# ProPrj_Sandro_OrangePi_CM5_Carrier_Board.net
KiCad netlist of a schematic drawn in EasyEDA Pro
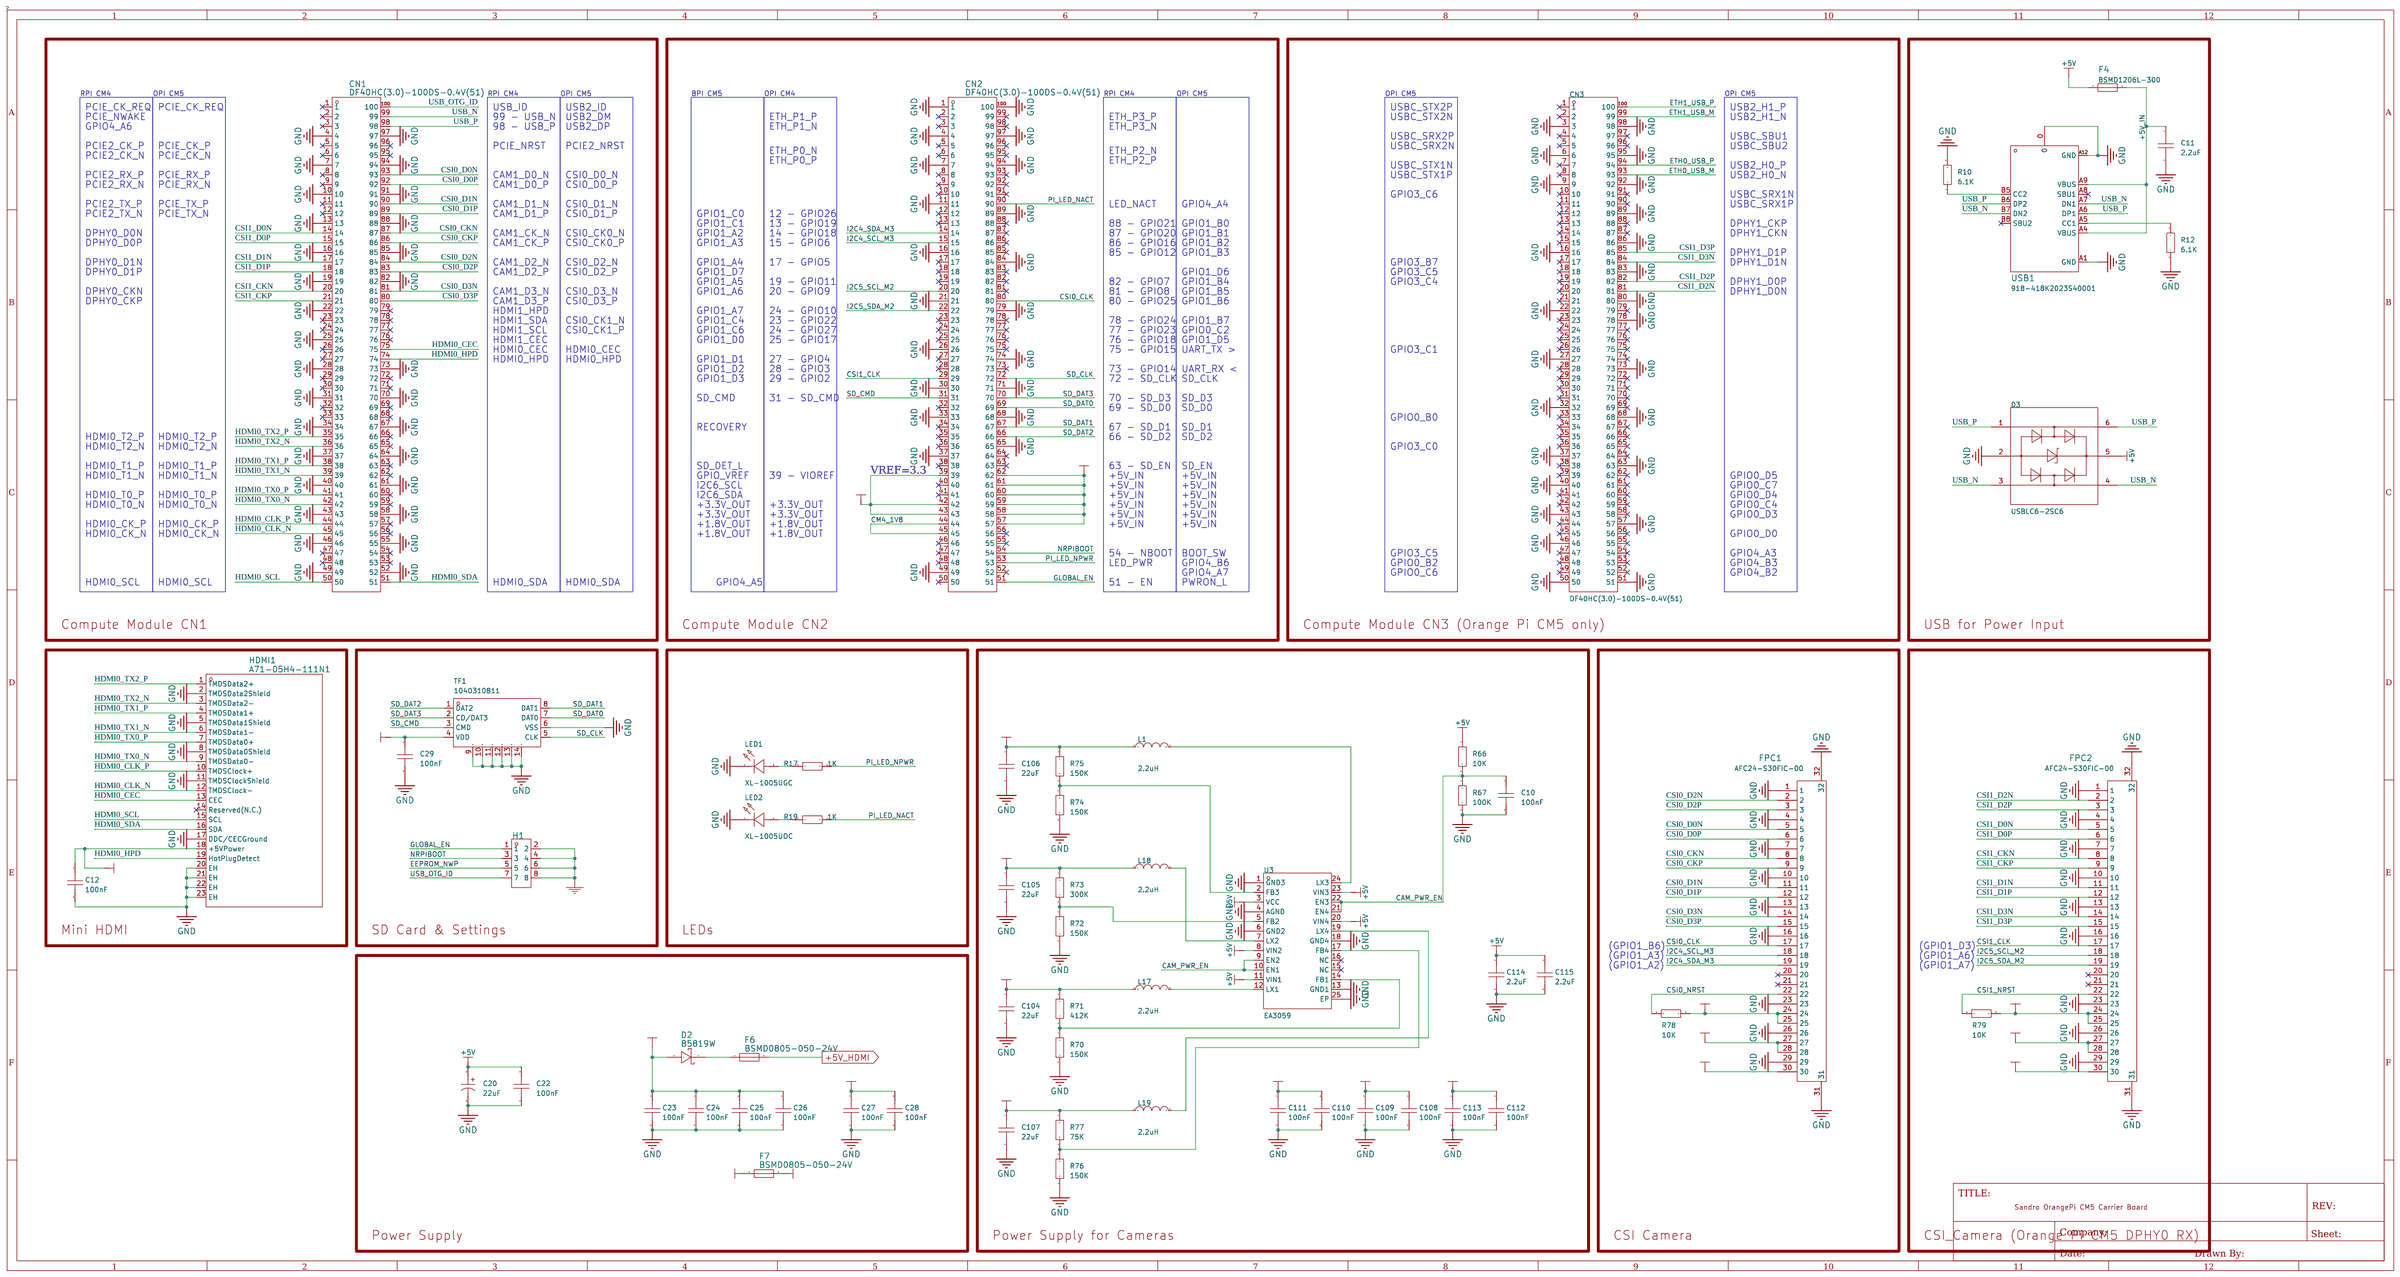
[diagram p0: CM4 Carrier]
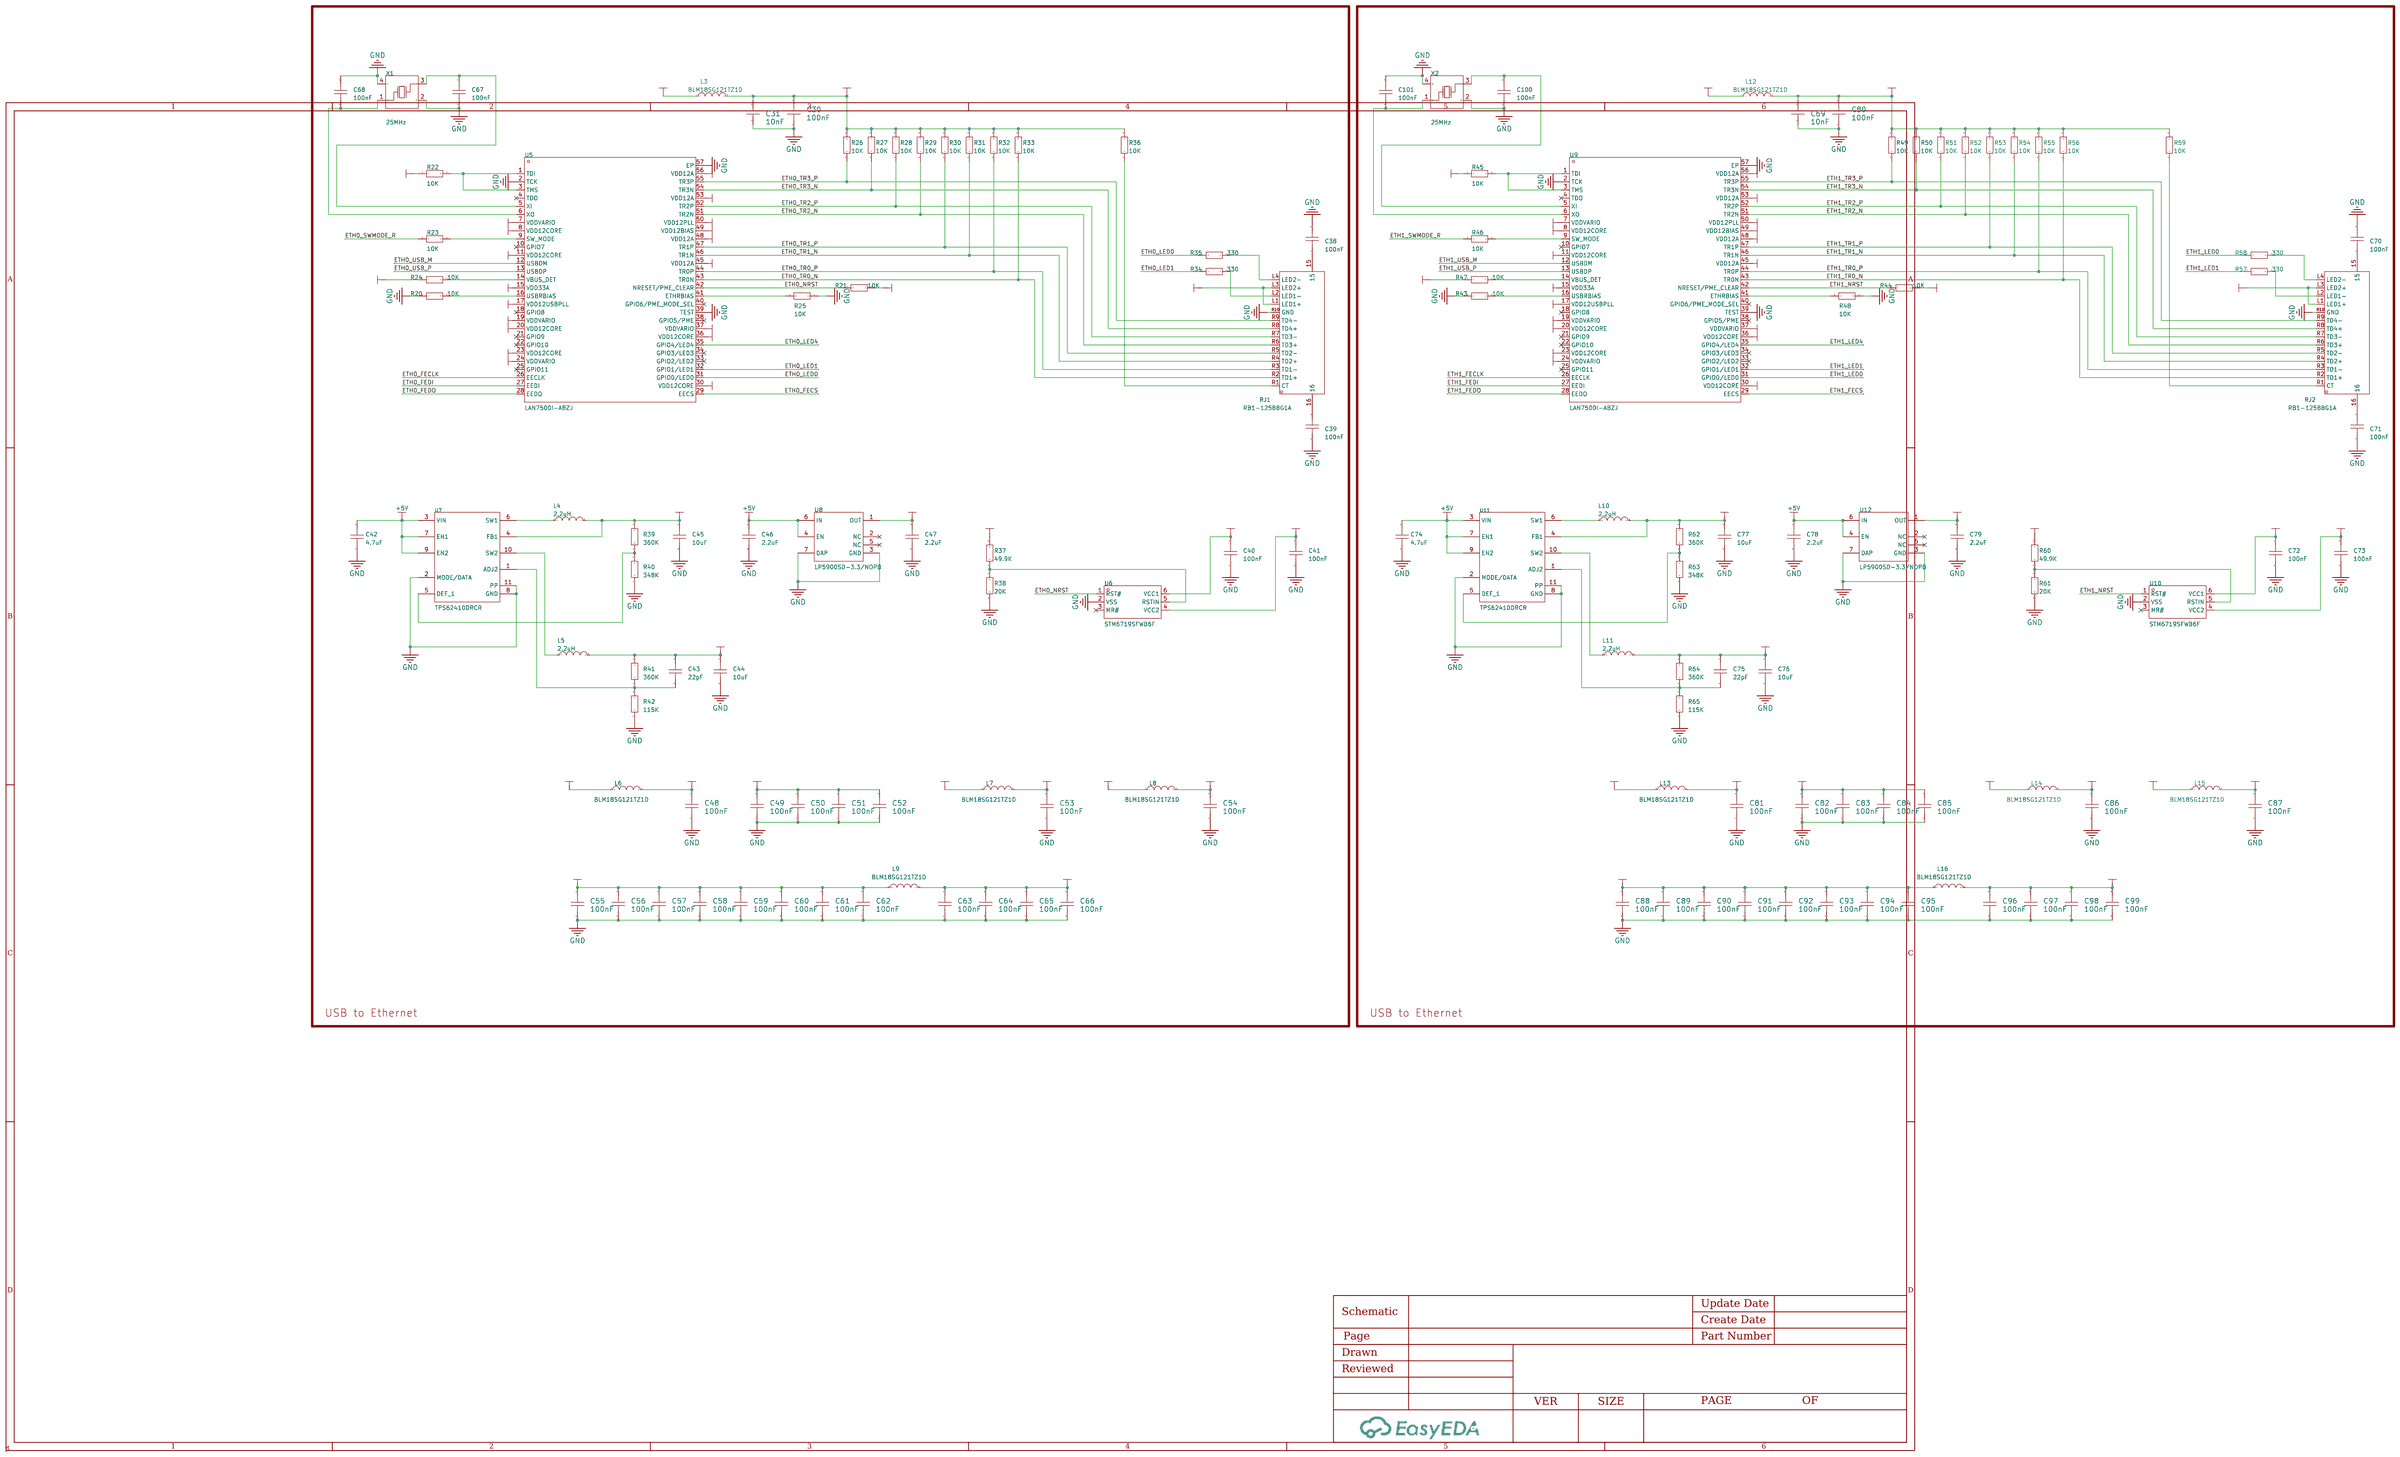
[diagram p1: 2.Ethernet]

(export (version "E")
  (design (tool "Eeschema 10.0.6"))
  (components
    (comp (ref "C10")
      (value "100nF")
      (footprint "easyedapro:C0402")
      (libsource (lib "easyedapro") (part "CAP"))
    )
    (comp (ref "C11")
      (value "2.2uF")
      (footprint "easyedapro:C0402")
      (libsource (lib "easyedapro") (part "CAP"))
    )
    (comp (ref "C12")
      (value "100nF")
      (footprint "easyedapro:C0402")
      (libsource (lib "easyedapro") (part "CAP"))
    )
    (comp (ref "C20")
      (value "22uF")
      (footprint "easyedapro:CAP-SMD_L3.2-W1.6")
      (fields
        (field (name "Manufacturer Part") "CA45-A-16V-22uF-K")
        (field (name "Manufacturer") "CEC(振华新云)")
      )
      (libsource (lib "easyedapro") (part "CA45-A-16V-22UF-K"))
    )
    (comp (ref "C22")
      (value "100nF")
      (footprint "easyedapro:C0402")
      (libsource (lib "easyedapro") (part "CAP"))
    )
    (comp (ref "C23")
      (value "100nF")
      (footprint "easyedapro:C0402")
      (libsource (lib "easyedapro") (part "CAP"))
    )
    (comp (ref "C24")
      (value "100nF")
      (footprint "easyedapro:C0402")
      (libsource (lib "easyedapro") (part "CAP"))
    )
    (comp (ref "C25")
      (value "100nF")
      (footprint "easyedapro:C0402")
      (libsource (lib "easyedapro") (part "CAP"))
    )
    (comp (ref "C26")
      (value "100nF")
      (footprint "easyedapro:C0402")
      (libsource (lib "easyedapro") (part "CAP"))
    )
    (comp (ref "C27")
      (value "100nF")
      (footprint "easyedapro:C0402")
      (libsource (lib "easyedapro") (part "CAP"))
    )
    (comp (ref "C28")
      (value "100nF")
      (footprint "easyedapro:C0402")
      (libsource (lib "easyedapro") (part "CAP"))
    )
    (comp (ref "C29")
      (value "100nF")
      (footprint "easyedapro:C0402")
      (libsource (lib "easyedapro") (part "CAP"))
    )
    (comp (ref "C104")
      (value "22uF")
      (footprint "easyedapro:C0402")
      (libsource (lib "easyedapro") (part "CAP"))
    )
    (comp (ref "C105")
      (value "22uF")
      (footprint "easyedapro:C0402")
      (libsource (lib "easyedapro") (part "CAP"))
    )
    (comp (ref "C106")
      (value "22uF")
      (footprint "easyedapro:C0402")
      (libsource (lib "easyedapro") (part "CAP"))
    )
    (comp (ref "C107")
      (value "22uF")
      (footprint "easyedapro:C0402")
      (libsource (lib "easyedapro") (part "CAP"))
    )
    (comp (ref "C108")
      (value "100nF")
      (footprint "easyedapro:C0402")
      (libsource (lib "easyedapro") (part "CAP"))
    )
    (comp (ref "C109")
      (value "100nF")
      (footprint "easyedapro:C0402")
      (libsource (lib "easyedapro") (part "CAP"))
    )
    (comp (ref "C110")
      (value "100nF")
      (footprint "easyedapro:C0402")
      (libsource (lib "easyedapro") (part "CAP"))
    )
    (comp (ref "C111")
      (value "100nF")
      (footprint "easyedapro:C0402")
      (libsource (lib "easyedapro") (part "CAP"))
    )
    (comp (ref "C112")
      (value "100nF")
      (footprint "easyedapro:C0402")
      (libsource (lib "easyedapro") (part "CAP"))
    )
    (comp (ref "C113")
      (value "100nF")
      (footprint "easyedapro:C0402")
      (libsource (lib "easyedapro") (part "CAP"))
    )
    (comp (ref "C114")
      (value "2.2uF")
      (footprint "easyedapro:C0402")
      (libsource (lib "easyedapro") (part "CAP"))
    )
    (comp (ref "C115")
      (value "2.2uF")
      (footprint "easyedapro:C0402")
      (libsource (lib "easyedapro") (part "CAP"))
    )
    (comp (ref "CN1")
      (value "DF40HC(3.0)-100DS-0.4V(51)")
      (footprint "easyedapro:CONN-SMD_DF40HC-3.0-100DS-0.4V-51")
      (fields (field (name "Manufacturer") "HRS(广濑)"))
      (libsource (lib "easyedapro") (part "DF40HC(3.0)-100DS-0.4V(51)"))
    )
    (comp (ref "CN2")
      (value "DF40HC(3.0)-100DS-0.4V(51)")
      (footprint "easyedapro:CONN-SMD_DF40HC-3.0-100DS-0.4V-51")
      (fields (field (name "Manufacturer") "HRS(广濑)"))
      (libsource (lib "easyedapro") (part "DF40HC(3.0)-100DS-0.4V(51)"))
    )
    (comp (ref "CN3")
      (value "DF40HC(3.0)-100DS-0.4V(51)")
      (footprint "easyedapro:CONN-SMD_DF40HC-3.0-100DS-0.4V-51")
      (fields (field (name "Manufacturer") "HRS(广濑)"))
      (libsource (lib "") (part "DF40HC(3.0)-100DS-0.4V(51)_1"))
    )
    (comp (ref "D2")
      (value "B5819W")
      (footprint "easyedapro:SOD-123_L2.7-W1.6-LS3.7-RD-1")
      (fields (field (name "Manufacturer") "CJ"))
      (libsource (lib "easyedapro") (part "B5819W"))
    )
    (comp (ref "D3")
      (value "USBLC6-2SC6")
      (footprint "easyedapro:SOT-23-6_L2.9-W1.6-P0.95-LS2.8-BL")
      (fields (field (name "Manufacturer") "ST(意法半导体)"))
      (libsource (lib "easyedapro") (part "USBLC6-2SC6"))
    )
    (comp (ref "F4")
      (value "BSMD1206L-300")
      (footprint "easyedapro:F1206")
      (fields (field (name "Manufacturer") "BHFUSE(佰宏)"))
      (libsource (lib "easyedapro") (part "BSMD1206L-300"))
    )
    (comp (ref "F6")
      (value "BSMD0805-050-24V")
      (footprint "easyedapro:F0805")
      (fields (field (name "Manufacturer") "BHFUSE"))
      (libsource (lib "easyedapro") (part "BSMD0805-050-24V"))
    )
    (comp (ref "F7")
      (value "BSMD0805-050-24V")
      (footprint "easyedapro:F0805")
      (fields (field (name "Manufacturer") "BHFUSE"))
      (libsource (lib "easyedapro") (part "BSMD0805-050-24V"))
    )
    (comp (ref "FPC1")
      (value "AFC24-S30FIC-00")
      (footprint "easyedapro:FPC-SMD_P0.50-30P_QCHF-SM-H2.0")
      (fields (field (name "Manufacturer") "JS(钜硕电子)"))
      (libsource (lib "easyedapro") (part "AFC24-S30FIC-00"))
    )
    (comp (ref "FPC2")
      (value "AFC24-S30FIC-00")
      (footprint "easyedapro:FPC-SMD_P0.50-30P_QCHF-SM-H2.0")
      (fields (field (name "Manufacturer") "JS(钜硕电子)"))
      (libsource (lib "easyedapro") (part "AFC24-S30FIC-00"))
    )
    (comp (ref "H1")
      (value "2.54-2*4P立贴针")
      (footprint "easyedapro:HDR-SMD_8P-P2.54-V-M-R2-C4-LS7.4")
      (fields (field (name "Manufacturer") "BOOMELE(博穆精密)"))
      (libsource (lib "easyedapro") (part "2.54-2*4P立贴针"))
    )
    (comp (ref "HDMI1")
      (value "A71-05H4-111N1")
      (footprint "easyedapro:HDMI-SMD_A71-05H4-111N1")
      (fields (field (name "Manufacturer") "XKB Connectivity(中国星坤)"))
      (libsource (lib "easyedapro") (part "A71-05H4-111N1"))
    )
    (comp (ref "L1")
      (value "2.2uH")
      (footprint "easyedapro:IND-SMD_L2.0-W1.6")
      (fields
        (field (name "Manufacturer Part") "CKCS201610-2.2uH/M")
        (field (name "Manufacturer") "CENKER(岑科)")
      )
      (libsource (lib "easyedapro") (part "CKCS201610-2.2UH/M-N"))
    )
    (comp (ref "L17")
      (value "2.2uH")
      (footprint "easyedapro:IND-SMD_L2.0-W1.6")
      (fields
        (field (name "Manufacturer Part") "CKCS201610-2.2uH/M")
        (field (name "Manufacturer") "CENKER(岑科)")
      )
      (libsource (lib "easyedapro") (part "CKCS201610-2.2UH/M-N"))
    )
    (comp (ref "L18")
      (value "2.2uH")
      (footprint "easyedapro:IND-SMD_L2.0-W1.6")
      (fields
        (field (name "Manufacturer Part") "CKCS201610-2.2uH/M")
        (field (name "Manufacturer") "CENKER(岑科)")
      )
      (libsource (lib "easyedapro") (part "CKCS201610-2.2UH/M-N"))
    )
    (comp (ref "L19")
      (value "2.2uH")
      (footprint "easyedapro:IND-SMD_L2.0-W1.6")
      (fields
        (field (name "Manufacturer Part") "CKCS201610-2.2uH/M")
        (field (name "Manufacturer") "CENKER(岑科)")
      )
      (libsource (lib "easyedapro") (part "CKCS201610-2.2UH/M-N"))
    )
    (comp (ref "LED1")
      (value "XL-1005UGC")
      (footprint "easyedapro:LED0402-RD_GREEN")
      (fields (field (name "Manufacturer") "XINGLIGHT(成兴光)"))
      (libsource (lib "easyedapro") (part "XL-1005UGC"))
    )
    (comp (ref "LED2")
      (value "XL-1005UOC")
      (footprint "easyedapro:LED0402-RD_ORANGE")
      (fields (field (name "Manufacturer") "XINGLIGHT(成兴光)"))
      (libsource (lib "easyedapro") (part "XL-1005UOC"))
    )
    (comp (ref "R10")
      (value "6.1K")
      (footprint "easyedapro:R0201")
      (libsource (lib "easyedapro") (part "Res"))
    )
    (comp (ref "R12")
      (value "6.1K")
      (footprint "easyedapro:R0201")
      (libsource (lib "easyedapro") (part "Res"))
    )
    (comp (ref "R17") (value "1K") (footprint "easyedapro:R0201") (libsource (lib "easyedapro") (part "Res")))
    (comp (ref "R19") (value "1K") (footprint "easyedapro:R0201") (libsource (lib "easyedapro") (part "Res")))
    (comp (ref "R66")
      (value "10K")
      (footprint "easyedapro:R0201")
      (libsource (lib "easyedapro") (part "Res"))
    )
    (comp (ref "R67")
      (value "100K")
      (footprint "easyedapro:R0201")
      (libsource (lib "easyedapro") (part "Res"))
    )
    (comp (ref "R70")
      (value "150K")
      (footprint "easyedapro:R0201")
      (libsource (lib "easyedapro") (part "Res"))
    )
    (comp (ref "R71")
      (value "412K")
      (footprint "easyedapro:R0201")
      (libsource (lib "easyedapro") (part "Res"))
    )
    (comp (ref "R72")
      (value "150K")
      (footprint "easyedapro:R0201")
      (libsource (lib "easyedapro") (part "Res"))
    )
    (comp (ref "R73")
      (value "300K")
      (footprint "easyedapro:R0201")
      (libsource (lib "easyedapro") (part "Res"))
    )
    (comp (ref "R74")
      (value "150K")
      (footprint "easyedapro:R0201")
      (libsource (lib "easyedapro") (part "Res"))
    )
    (comp (ref "R75")
      (value "150K")
      (footprint "easyedapro:R0201")
      (libsource (lib "easyedapro") (part "Res"))
    )
    (comp (ref "R76")
      (value "150K")
      (footprint "easyedapro:R0201")
      (libsource (lib "easyedapro") (part "Res"))
    )
    (comp (ref "R77")
      (value "75K")
      (footprint "easyedapro:R0201")
      (libsource (lib "easyedapro") (part "Res"))
    )
    (comp (ref "R78")
      (value "10K")
      (footprint "easyedapro:R0201")
      (libsource (lib "easyedapro") (part "Res"))
    )
    (comp (ref "R79")
      (value "10K")
      (footprint "easyedapro:R0201")
      (libsource (lib "easyedapro") (part "Res"))
    )
    (comp (ref "TF1")
      (value "1040310811")
      (footprint "easyedapro:SIM-SMD_8P-1040310811")
      (fields (field (name "Manufacturer") "MOLEX"))
      (libsource (lib "easyedapro") (part "1040310811"))
    )
    (comp (ref "U3")
      (value "EA3059")
      (footprint "easyedapro:VQFN-24_L4.0-W4.0-P0.50-TL-EP2.5")
      (fields (field (name "Manufacturer") "everanalog(申风)"))
      (libsource (lib "easyedapro") (part "EA3059"))
    )
    (comp (ref "USB1")
      (value "918-418K2023S40001")
      (footprint "easyedapro:USB-C-SMD_TYPE-C-USB-17")
      (fields (field (name "Manufacturer") "精拓金"))
      (libsource (lib "easyedapro") (part "USB3.1C16PFSMT"))
    )
    (comp (ref "C30")
      (value "100nF")
      (footprint "easyedapro:C0402")
      (fields
        (field (name "Manufacturer Part") "GRM155R71H104KE14D")
        (field (name "Manufacturer") "muRata(村田)")
      )
      (libsource (lib "easyedapro") (part "GRM155R71H104KE14D"))
    )
    (comp (ref "C31")
      (value "10nF")
      (footprint "easyedapro:C0402")
      (fields
        (field (name "Manufacturer Part") "GRM155R71H103KA88D")
        (field (name "Manufacturer") "muRata(村田)")
      )
      (libsource (lib "easyedapro") (part "GRM155R71H103KA88D"))
    )
    (comp (ref "C38")
      (value "100nF")
      (footprint "easyedapro:C0402")
      (libsource (lib "easyedapro") (part "CAP"))
    )
    (comp (ref "C39")
      (value "100nF")
      (footprint "easyedapro:C0402")
      (libsource (lib "easyedapro") (part "CAP"))
    )
    (comp (ref "C40")
      (value "100nF")
      (footprint "easyedapro:C0402")
      (libsource (lib "easyedapro") (part "CAP"))
    )
    (comp (ref "C41")
      (value "100nF")
      (footprint "easyedapro:C0402")
      (libsource (lib "easyedapro") (part "CAP"))
    )
    (comp (ref "C42")
      (value "4.7uF")
      (footprint "easyedapro:C0603")
      (fields
        (field (name "Manufacturer Part") "GRM188Z71C475KE21D")
        (field (name "Manufacturer") "muRata(村田)")
      )
      (libsource (lib "easyedapro") (part "GRM188Z71C475KE21D"))
    )
    (comp (ref "C43")
      (value "22pF")
      (footprint "easyedapro:C0402")
      (libsource (lib "easyedapro") (part "CAP"))
    )
    (comp (ref "C44")
      (value "10uF")
      (footprint "easyedapro:C0402")
      (libsource (lib "easyedapro") (part "CAP"))
    )
    (comp (ref "C45")
      (value "10uF")
      (footprint "easyedapro:C0402")
      (libsource (lib "easyedapro") (part "CAP"))
    )
    (comp (ref "C46")
      (value "2.2uF")
      (footprint "easyedapro:C0402")
      (libsource (lib "easyedapro") (part "CAP"))
    )
    (comp (ref "C47")
      (value "2.2uF")
      (footprint "easyedapro:C0402")
      (libsource (lib "easyedapro") (part "CAP"))
    )
    (comp (ref "C48")
      (value "100nF")
      (footprint "easyedapro:C0402")
      (fields
        (field (name "Manufacturer Part") "GRM155R71H104KE14D")
        (field (name "Manufacturer") "muRata(村田)")
        (field (name "Tolerance") "±10%")
      )
      (libsource (lib "easyedapro") (part "GRM155R71H104KE14D"))
    )
    (comp (ref "C49")
      (value "100nF")
      (footprint "easyedapro:C0402")
      (fields
        (field (name "Manufacturer Part") "GRM155R71H104KE14D")
        (field (name "Manufacturer") "muRata(村田)")
        (field (name "Tolerance") "±10%")
      )
      (libsource (lib "easyedapro") (part "GRM155R71H104KE14D"))
    )
    (comp (ref "C50")
      (value "100nF")
      (footprint "easyedapro:C0402")
      (fields
        (field (name "Manufacturer Part") "GRM155R71H104KE14D")
        (field (name "Manufacturer") "muRata(村田)")
        (field (name "Tolerance") "±10%")
      )
      (libsource (lib "easyedapro") (part "GRM155R71H104KE14D"))
    )
    (comp (ref "C51")
      (value "100nF")
      (footprint "easyedapro:C0402")
      (fields
        (field (name "Manufacturer Part") "GRM155R71H104KE14D")
        (field (name "Manufacturer") "muRata(村田)")
        (field (name "Tolerance") "±10%")
      )
      (libsource (lib "easyedapro") (part "GRM155R71H104KE14D"))
    )
    (comp (ref "C52")
      (value "100nF")
      (footprint "easyedapro:C0402")
      (fields
        (field (name "Manufacturer Part") "GRM155R71H104KE14D")
        (field (name "Manufacturer") "muRata(村田)")
        (field (name "Tolerance") "±10%")
      )
      (libsource (lib "easyedapro") (part "GRM155R71H104KE14D"))
    )
    (comp (ref "C53")
      (value "100nF")
      (footprint "easyedapro:C0402")
      (fields
        (field (name "Manufacturer Part") "GRM155R71H104KE14D")
        (field (name "Manufacturer") "muRata(村田)")
        (field (name "Tolerance") "±10%")
      )
      (libsource (lib "easyedapro") (part "GRM155R71H104KE14D"))
    )
    (comp (ref "C54")
      (value "100nF")
      (footprint "easyedapro:C0402")
      (fields
        (field (name "Manufacturer Part") "GRM155R71H104KE14D")
        (field (name "Manufacturer") "muRata(村田)")
        (field (name "Tolerance") "±10%")
      )
      (libsource (lib "easyedapro") (part "GRM155R71H104KE14D"))
    )
    (comp (ref "C55")
      (value "100nF")
      (footprint "easyedapro:C0402")
      (fields
        (field (name "Manufacturer Part") "GRM155R71H104KE14D")
        (field (name "Manufacturer") "muRata(村田)")
        (field (name "Tolerance") "±10%")
      )
      (libsource (lib "easyedapro") (part "GRM155R71H104KE14D"))
    )
    (comp (ref "C56")
      (value "100nF")
      (footprint "easyedapro:C0402")
      (fields
        (field (name "Manufacturer Part") "GRM155R71H104KE14D")
        (field (name "Manufacturer") "muRata(村田)")
        (field (name "Tolerance") "±10%")
      )
      (libsource (lib "easyedapro") (part "GRM155R71H104KE14D"))
    )
    (comp (ref "C57")
      (value "100nF")
      (footprint "easyedapro:C0402")
      (fields
        (field (name "Manufacturer Part") "GRM155R71H104KE14D")
        (field (name "Manufacturer") "muRata(村田)")
        (field (name "Tolerance") "±10%")
      )
      (libsource (lib "easyedapro") (part "GRM155R71H104KE14D"))
    )
    (comp (ref "C58")
      (value "100nF")
      (footprint "easyedapro:C0402")
      (fields
        (field (name "Manufacturer Part") "GRM155R71H104KE14D")
        (field (name "Manufacturer") "muRata(村田)")
        (field (name "Tolerance") "±10%")
      )
      (libsource (lib "easyedapro") (part "GRM155R71H104KE14D"))
    )
    (comp (ref "C59")
      (value "100nF")
      (footprint "easyedapro:C0402")
      (fields
        (field (name "Manufacturer Part") "GRM155R71H104KE14D")
        (field (name "Manufacturer") "muRata(村田)")
        (field (name "Tolerance") "±10%")
      )
      (libsource (lib "easyedapro") (part "GRM155R71H104KE14D"))
    )
    (comp (ref "C60")
      (value "100nF")
      (footprint "easyedapro:C0402")
      (fields
        (field (name "Manufacturer Part") "GRM155R71H104KE14D")
        (field (name "Manufacturer") "muRata(村田)")
        (field (name "Tolerance") "±10%")
      )
      (libsource (lib "easyedapro") (part "GRM155R71H104KE14D"))
    )
    (comp (ref "C61")
      (value "100nF")
      (footprint "easyedapro:C0402")
      (fields
        (field (name "Manufacturer Part") "GRM155R71H104KE14D")
        (field (name "Manufacturer") "muRata(村田)")
        (field (name "Tolerance") "±10%")
      )
      (libsource (lib "easyedapro") (part "GRM155R71H104KE14D"))
    )
    (comp (ref "C62")
      (value "100nF")
      (footprint "easyedapro:C0402")
      (fields
        (field (name "Manufacturer Part") "GRM155R71H104KE14D")
        (field (name "Manufacturer") "muRata(村田)")
        (field (name "Tolerance") "±10%")
      )
      (libsource (lib "easyedapro") (part "GRM155R71H104KE14D"))
    )
    (comp (ref "C63")
      (value "100nF")
      (footprint "easyedapro:C0402")
      (fields
        (field (name "Manufacturer Part") "GRM155R71H104KE14D")
        (field (name "Manufacturer") "muRata(村田)")
        (field (name "Tolerance") "±10%")
      )
      (libsource (lib "easyedapro") (part "GRM155R71H104KE14D"))
    )
    (comp (ref "C64")
      (value "100nF")
      (footprint "easyedapro:C0402")
      (fields
        (field (name "Manufacturer Part") "GRM155R71H104KE14D")
        (field (name "Manufacturer") "muRata(村田)")
        (field (name "Tolerance") "±10%")
      )
      (libsource (lib "easyedapro") (part "GRM155R71H104KE14D"))
    )
    (comp (ref "C65")
      (value "100nF")
      (footprint "easyedapro:C0402")
      (fields
        (field (name "Manufacturer Part") "GRM155R71H104KE14D")
        (field (name "Manufacturer") "muRata(村田)")
        (field (name "Tolerance") "±10%")
      )
      (libsource (lib "easyedapro") (part "GRM155R71H104KE14D"))
    )
    (comp (ref "C66")
      (value "100nF")
      (footprint "easyedapro:C0402")
      (fields
        (field (name "Manufacturer Part") "GRM155R71H104KE14D")
        (field (name "Manufacturer") "muRata(村田)")
        (field (name "Tolerance") "±10%")
      )
      (libsource (lib "easyedapro") (part "GRM155R71H104KE14D"))
    )
    (comp (ref "C67")
      (value "100nF")
      (footprint "easyedapro:C0402")
      (libsource (lib "easyedapro") (part "CAP"))
    )
    (comp (ref "C68")
      (value "100nF")
      (footprint "easyedapro:C0402")
      (libsource (lib "easyedapro") (part "CAP"))
    )
    (comp (ref "C69")
      (value "10nF")
      (footprint "easyedapro:C0402")
      (fields
        (field (name "Manufacturer Part") "GRM155R71H103KA88D")
        (field (name "Manufacturer") "muRata(村田)")
      )
      (libsource (lib "easyedapro") (part "GRM155R71H103KA88D"))
    )
    (comp (ref "C70")
      (value "100nF")
      (footprint "easyedapro:C0402")
      (libsource (lib "easyedapro") (part "CAP"))
    )
    (comp (ref "C71")
      (value "100nF")
      (footprint "easyedapro:C0402")
      (libsource (lib "easyedapro") (part "CAP"))
    )
    (comp (ref "C72")
      (value "100nF")
      (footprint "easyedapro:C0402")
      (libsource (lib "easyedapro") (part "CAP"))
    )
    (comp (ref "C73")
      (value "100nF")
      (footprint "easyedapro:C0402")
      (libsource (lib "easyedapro") (part "CAP"))
    )
    (comp (ref "C74")
      (value "4.7uF")
      (footprint "easyedapro:C0603")
      (fields
        (field (name "Manufacturer Part") "GRM188Z71C475KE21D")
        (field (name "Manufacturer") "muRata(村田)")
      )
      (libsource (lib "easyedapro") (part "GRM188Z71C475KE21D"))
    )
    (comp (ref "C75")
      (value "22pF")
      (footprint "easyedapro:C0402")
      (libsource (lib "easyedapro") (part "CAP"))
    )
    (comp (ref "C76")
      (value "10uF")
      (footprint "easyedapro:C0402")
      (libsource (lib "easyedapro") (part "CAP"))
    )
    (comp (ref "C77")
      (value "10uF")
      (footprint "easyedapro:C0402")
      (libsource (lib "easyedapro") (part "CAP"))
    )
    (comp (ref "C78")
      (value "2.2uF")
      (footprint "easyedapro:C0402")
      (libsource (lib "easyedapro") (part "CAP"))
    )
    (comp (ref "C79")
      (value "2.2uF")
      (footprint "easyedapro:C0402")
      (libsource (lib "easyedapro") (part "CAP"))
    )
    (comp (ref "C80")
      (value "100nF")
      (footprint "easyedapro:C0402")
      (fields
        (field (name "Manufacturer Part") "GRM155R71H104KE14D")
        (field (name "Manufacturer") "muRata(村田)")
      )
      (libsource (lib "easyedapro") (part "GRM155R71H104KE14D"))
    )
    (comp (ref "C81")
      (value "100nF")
      (footprint "easyedapro:C0402")
      (fields
        (field (name "Manufacturer Part") "GRM155R71H104KE14D")
        (field (name "Manufacturer") "muRata(村田)")
        (field (name "Tolerance") "±10%")
      )
      (libsource (lib "easyedapro") (part "GRM155R71H104KE14D"))
    )
    (comp (ref "C82")
      (value "100nF")
      (footprint "easyedapro:C0402")
      (fields
        (field (name "Manufacturer Part") "GRM155R71H104KE14D")
        (field (name "Manufacturer") "muRata(村田)")
        (field (name "Tolerance") "±10%")
      )
      (libsource (lib "easyedapro") (part "GRM155R71H104KE14D"))
    )
    (comp (ref "C83")
      (value "100nF")
      (footprint "easyedapro:C0402")
      (fields
        (field (name "Manufacturer Part") "GRM155R71H104KE14D")
        (field (name "Manufacturer") "muRata(村田)")
        (field (name "Tolerance") "±10%")
      )
      (libsource (lib "easyedapro") (part "GRM155R71H104KE14D"))
    )
    (comp (ref "C84")
      (value "100nF")
      (footprint "easyedapro:C0402")
      (fields
        (field (name "Manufacturer Part") "GRM155R71H104KE14D")
        (field (name "Manufacturer") "muRata(村田)")
        (field (name "Tolerance") "±10%")
      )
      (libsource (lib "easyedapro") (part "GRM155R71H104KE14D"))
    )
    (comp (ref "C85")
      (value "100nF")
      (footprint "easyedapro:C0402")
      (fields
        (field (name "Manufacturer Part") "GRM155R71H104KE14D")
        (field (name "Manufacturer") "muRata(村田)")
        (field (name "Tolerance") "±10%")
      )
      (libsource (lib "easyedapro") (part "GRM155R71H104KE14D"))
    )
    (comp (ref "C86")
      (value "100nF")
      (footprint "easyedapro:C0402")
      (fields
        (field (name "Manufacturer Part") "GRM155R71H104KE14D")
        (field (name "Manufacturer") "muRata(村田)")
        (field (name "Tolerance") "±10%")
      )
      (libsource (lib "easyedapro") (part "GRM155R71H104KE14D"))
    )
    (comp (ref "C87")
      (value "100nF")
      (footprint "easyedapro:C0402")
      (fields
        (field (name "Manufacturer Part") "GRM155R71H104KE14D")
        (field (name "Manufacturer") "muRata(村田)")
        (field (name "Tolerance") "±10%")
      )
      (libsource (lib "easyedapro") (part "GRM155R71H104KE14D"))
    )
    (comp (ref "C88")
      (value "100nF")
      (footprint "easyedapro:C0402")
      (fields
        (field (name "Manufacturer Part") "GRM155R71H104KE14D")
        (field (name "Manufacturer") "muRata(村田)")
        (field (name "Tolerance") "±10%")
      )
      (libsource (lib "easyedapro") (part "GRM155R71H104KE14D"))
    )
    (comp (ref "C89")
      (value "100nF")
      (footprint "easyedapro:C0402")
      (fields
        (field (name "Manufacturer Part") "GRM155R71H104KE14D")
        (field (name "Manufacturer") "muRata(村田)")
        (field (name "Tolerance") "±10%")
      )
      (libsource (lib "easyedapro") (part "GRM155R71H104KE14D"))
    )
    (comp (ref "C90")
      (value "100nF")
      (footprint "easyedapro:C0402")
      (fields
        (field (name "Manufacturer Part") "GRM155R71H104KE14D")
        (field (name "Manufacturer") "muRata(村田)")
        (field (name "Tolerance") "±10%")
      )
      (libsource (lib "easyedapro") (part "GRM155R71H104KE14D"))
    )
    (comp (ref "C91")
      (value "100nF")
      (footprint "easyedapro:C0402")
      (fields
        (field (name "Manufacturer Part") "GRM155R71H104KE14D")
        (field (name "Manufacturer") "muRata(村田)")
        (field (name "Tolerance") "±10%")
      )
      (libsource (lib "easyedapro") (part "GRM155R71H104KE14D"))
    )
    (comp (ref "C92")
      (value "100nF")
      (footprint "easyedapro:C0402")
      (fields
        (field (name "Manufacturer Part") "GRM155R71H104KE14D")
        (field (name "Manufacturer") "muRata(村田)")
        (field (name "Tolerance") "±10%")
      )
      (libsource (lib "easyedapro") (part "GRM155R71H104KE14D"))
    )
    (comp (ref "C93")
      (value "100nF")
      (footprint "easyedapro:C0402")
      (fields
        (field (name "Manufacturer Part") "GRM155R71H104KE14D")
        (field (name "Manufacturer") "muRata(村田)")
        (field (name "Tolerance") "±10%")
      )
      (libsource (lib "easyedapro") (part "GRM155R71H104KE14D"))
    )
    (comp (ref "C94")
      (value "100nF")
      (footprint "easyedapro:C0402")
      (fields
        (field (name "Manufacturer Part") "GRM155R71H104KE14D")
        (field (name "Manufacturer") "muRata(村田)")
        (field (name "Tolerance") "±10%")
      )
      (libsource (lib "easyedapro") (part "GRM155R71H104KE14D"))
    )
    (comp (ref "C95")
      (value "100nF")
      (footprint "easyedapro:C0402")
      (fields
        (field (name "Manufacturer Part") "GRM155R71H104KE14D")
        (field (name "Manufacturer") "muRata(村田)")
        (field (name "Tolerance") "±10%")
      )
      (libsource (lib "easyedapro") (part "GRM155R71H104KE14D"))
    )
    (comp (ref "C96")
      (value "100nF")
      (footprint "easyedapro:C0402")
      (fields
        (field (name "Manufacturer Part") "GRM155R71H104KE14D")
        (field (name "Manufacturer") "muRata(村田)")
        (field (name "Tolerance") "±10%")
      )
      (libsource (lib "easyedapro") (part "GRM155R71H104KE14D"))
    )
    (comp (ref "C97")
      (value "100nF")
      (footprint "easyedapro:C0402")
      (fields
        (field (name "Manufacturer Part") "GRM155R71H104KE14D")
        (field (name "Manufacturer") "muRata(村田)")
        (field (name "Tolerance") "±10%")
      )
      (libsource (lib "easyedapro") (part "GRM155R71H104KE14D"))
    )
    (comp (ref "C98")
      (value "100nF")
      (footprint "easyedapro:C0402")
      (fields
        (field (name "Manufacturer Part") "GRM155R71H104KE14D")
        (field (name "Manufacturer") "muRata(村田)")
        (field (name "Tolerance") "±10%")
      )
      (libsource (lib "easyedapro") (part "GRM155R71H104KE14D"))
    )
    (comp (ref "C99")
      (value "100nF")
      (footprint "easyedapro:C0402")
      (fields
        (field (name "Manufacturer Part") "GRM155R71H104KE14D")
        (field (name "Manufacturer") "muRata(村田)")
        (field (name "Tolerance") "±10%")
      )
      (libsource (lib "easyedapro") (part "GRM155R71H104KE14D"))
    )
    (comp (ref "C100")
      (value "100nF")
      (footprint "easyedapro:C0402")
      (libsource (lib "easyedapro") (part "CAP"))
    )
    (comp (ref "C101")
      (value "100nF")
      (footprint "easyedapro:C0402")
      (libsource (lib "easyedapro") (part "CAP"))
    )
    (comp (ref "L3")
      (value "BLM18SG121TZ1D")
      (footprint "easyedapro:L0603")
      (fields (field (name "Manufacturer") "muRata(村田)"))
      (libsource (lib "easyedapro") (part "BLM18SG121TZ1D"))
    )
    (comp (ref "L4")
      (value "2.2uH")
      (footprint "easyedapro:IND-SMD_L2.0-W1.6")
      (fields
        (field (name "Manufacturer Part") "CKCS201610-2.2uH/M")
        (field (name "Manufacturer") "CENKER(岑科)")
      )
      (libsource (lib "easyedapro") (part "CKCS201610-2.2UH/M-N"))
    )
    (comp (ref "L5")
      (value "2.2uH")
      (footprint "easyedapro:IND-SMD_L2.0-W1.6")
      (fields
        (field (name "Manufacturer Part") "CKCS201610-2.2uH/M")
        (field (name "Manufacturer") "CENKER(岑科)")
      )
      (libsource (lib "easyedapro") (part "CKCS201610-2.2UH/M-N"))
    )
    (comp (ref "L6")
      (value "BLM18SG121TZ1D")
      (footprint "easyedapro:L0603")
      (fields (field (name "Manufacturer") "muRata(村田)"))
      (libsource (lib "easyedapro") (part "BLM18SG121TZ1D"))
    )
    (comp (ref "L7")
      (value "BLM18SG121TZ1D")
      (footprint "easyedapro:L0603")
      (fields (field (name "Manufacturer") "muRata(村田)"))
      (libsource (lib "easyedapro") (part "BLM18SG121TZ1D"))
    )
    (comp (ref "L8")
      (value "BLM18SG121TZ1D")
      (footprint "easyedapro:L0603")
      (fields (field (name "Manufacturer") "muRata(村田)"))
      (libsource (lib "easyedapro") (part "BLM18SG121TZ1D"))
    )
    (comp (ref "L9")
      (value "BLM18SG121TZ1D")
      (footprint "easyedapro:L0603")
      (fields (field (name "Manufacturer") "muRata(村田)"))
      (libsource (lib "easyedapro") (part "BLM18SG121TZ1D"))
    )
    (comp (ref "L10")
      (value "2.2uH")
      (footprint "easyedapro:IND-SMD_L2.0-W1.6")
      (fields
        (field (name "Manufacturer Part") "CKCS201610-2.2uH/M")
        (field (name "Manufacturer") "CENKER(岑科)")
      )
      (libsource (lib "easyedapro") (part "CKCS201610-2.2UH/M-N"))
    )
    (comp (ref "L11")
      (value "2.2uH")
      (footprint "easyedapro:IND-SMD_L2.0-W1.6")
      (fields
        (field (name "Manufacturer Part") "CKCS201610-2.2uH/M")
        (field (name "Manufacturer") "CENKER(岑科)")
      )
      (libsource (lib "easyedapro") (part "CKCS201610-2.2UH/M-N"))
    )
    (comp (ref "L12")
      (value "BLM18SG121TZ1D")
      (footprint "easyedapro:L0603")
      (fields (field (name "Manufacturer") "muRata(村田)"))
      (libsource (lib "easyedapro") (part "BLM18SG121TZ1D"))
    )
    (comp (ref "L13")
      (value "BLM18SG121TZ1D")
      (footprint "easyedapro:L0603")
      (fields (field (name "Manufacturer") "muRata(村田)"))
      (libsource (lib "easyedapro") (part "BLM18SG121TZ1D"))
    )
    (comp (ref "L14")
      (value "BLM18SG121TZ1D")
      (footprint "easyedapro:L0603")
      (fields (field (name "Manufacturer") "muRata(村田)"))
      (libsource (lib "easyedapro") (part "BLM18SG121TZ1D"))
    )
    (comp (ref "L15")
      (value "BLM18SG121TZ1D")
      (footprint "easyedapro:L0603")
      (fields (field (name "Manufacturer") "muRata(村田)"))
      (libsource (lib "easyedapro") (part "BLM18SG121TZ1D"))
    )
    (comp (ref "L16")
      (value "BLM18SG121TZ1D")
      (footprint "easyedapro:L0603")
      (fields (field (name "Manufacturer") "muRata(村田)"))
      (libsource (lib "easyedapro") (part "BLM18SG121TZ1D"))
    )
    (comp (ref "R20")
      (value "10K")
      (footprint "easyedapro:R0201")
      (libsource (lib "easyedapro") (part "Res"))
    )
    (comp (ref "R21")
      (value "10K")
      (footprint "easyedapro:R0201")
      (libsource (lib "easyedapro") (part "Res"))
    )
    (comp (ref "R22")
      (value "10K")
      (footprint "easyedapro:R0201")
      (libsource (lib "easyedapro") (part "Res"))
    )
    (comp (ref "R23")
      (value "10K")
      (footprint "easyedapro:R0201")
      (libsource (lib "easyedapro") (part "Res"))
    )
    (comp (ref "R24")
      (value "10K")
      (footprint "easyedapro:R0201")
      (libsource (lib "easyedapro") (part "Res"))
    )
    (comp (ref "R25")
      (value "10K")
      (footprint "easyedapro:R0201")
      (libsource (lib "easyedapro") (part "Res"))
    )
    (comp (ref "R26")
      (value "10K")
      (footprint "easyedapro:R0201")
      (libsource (lib "easyedapro") (part "Res"))
    )
    (comp (ref "R27")
      (value "10K")
      (footprint "easyedapro:R0201")
      (libsource (lib "easyedapro") (part "Res"))
    )
    (comp (ref "R28")
      (value "10K")
      (footprint "easyedapro:R0201")
      (libsource (lib "easyedapro") (part "Res"))
    )
    (comp (ref "R29")
      (value "10K")
      (footprint "easyedapro:R0201")
      (libsource (lib "easyedapro") (part "Res"))
    )
    (comp (ref "R30")
      (value "10K")
      (footprint "easyedapro:R0201")
      (libsource (lib "easyedapro") (part "Res"))
    )
    (comp (ref "R31")
      (value "10K")
      (footprint "easyedapro:R0201")
      (libsource (lib "easyedapro") (part "Res"))
    )
    (comp (ref "R32")
      (value "10K")
      (footprint "easyedapro:R0201")
      (libsource (lib "easyedapro") (part "Res"))
    )
    (comp (ref "R33")
      (value "10K")
      (footprint "easyedapro:R0201")
      (libsource (lib "easyedapro") (part "Res"))
    )
    (comp (ref "R34")
      (value "330")
      (footprint "easyedapro:R0201")
      (libsource (lib "easyedapro") (part "Res"))
    )
    (comp (ref "R35")
      (value "330")
      (footprint "easyedapro:R0201")
      (libsource (lib "easyedapro") (part "Res"))
    )
    (comp (ref "R36")
      (value "10K")
      (footprint "easyedapro:R0201")
      (libsource (lib "easyedapro") (part "Res"))
    )
    (comp (ref "R37")
      (value "49.9K")
      (footprint "easyedapro:R0201")
      (libsource (lib "easyedapro") (part "Res"))
    )
    (comp (ref "R38")
      (value "20K")
      (footprint "easyedapro:R0201")
      (libsource (lib "easyedapro") (part "Res"))
    )
    (comp (ref "R39")
      (value "360K")
      (footprint "easyedapro:R0201")
      (libsource (lib "easyedapro") (part "Res"))
    )
    (comp (ref "R40")
      (value "348K")
      (footprint "easyedapro:R0201")
      (libsource (lib "easyedapro") (part "Res"))
    )
    (comp (ref "R41")
      (value "360K")
      (footprint "easyedapro:R0201")
      (libsource (lib "easyedapro") (part "Res"))
    )
    (comp (ref "R42")
      (value "115K")
      (footprint "easyedapro:R0201")
      (libsource (lib "easyedapro") (part "Res"))
    )
    (comp (ref "R43")
      (value "10K")
      (footprint "easyedapro:R0201")
      (libsource (lib "easyedapro") (part "Res"))
    )
    (comp (ref "R44")
      (value "10K")
      (footprint "easyedapro:R0201")
      (libsource (lib "easyedapro") (part "Res"))
    )
    (comp (ref "R45")
      (value "10K")
      (footprint "easyedapro:R0201")
      (libsource (lib "easyedapro") (part "Res"))
    )
    (comp (ref "R46")
      (value "10K")
      (footprint "easyedapro:R0201")
      (libsource (lib "easyedapro") (part "Res"))
    )
    (comp (ref "R47")
      (value "10K")
      (footprint "easyedapro:R0201")
      (libsource (lib "easyedapro") (part "Res"))
    )
    (comp (ref "R48")
      (value "10K")
      (footprint "easyedapro:R0201")
      (libsource (lib "easyedapro") (part "Res"))
    )
    (comp (ref "R49")
      (value "10K")
      (footprint "easyedapro:R0201")
      (libsource (lib "easyedapro") (part "Res"))
    )
    (comp (ref "R50")
      (value "10K")
      (footprint "easyedapro:R0201")
      (libsource (lib "easyedapro") (part "Res"))
    )
    (comp (ref "R51")
      (value "10K")
      (footprint "easyedapro:R0201")
      (libsource (lib "easyedapro") (part "Res"))
    )
    (comp (ref "R52")
      (value "10K")
      (footprint "easyedapro:R0201")
      (libsource (lib "easyedapro") (part "Res"))
    )
    (comp (ref "R53")
      (value "10K")
      (footprint "easyedapro:R0201")
      (libsource (lib "easyedapro") (part "Res"))
    )
    (comp (ref "R54")
      (value "10K")
      (footprint "easyedapro:R0201")
      (libsource (lib "easyedapro") (part "Res"))
    )
    (comp (ref "R55")
      (value "10K")
      (footprint "easyedapro:R0201")
      (libsource (lib "easyedapro") (part "Res"))
    )
    (comp (ref "R56")
      (value "10K")
      (footprint "easyedapro:R0201")
      (libsource (lib "easyedapro") (part "Res"))
    )
    (comp (ref "R57")
      (value "330")
      (footprint "easyedapro:R0201")
      (libsource (lib "easyedapro") (part "Res"))
    )
    (comp (ref "R58")
      (value "330")
      (footprint "easyedapro:R0201")
      (libsource (lib "easyedapro") (part "Res"))
    )
    (comp (ref "R59")
      (value "10K")
      (footprint "easyedapro:R0201")
      (libsource (lib "easyedapro") (part "Res"))
    )
    (comp (ref "R60")
      (value "49.9K")
      (footprint "easyedapro:R0201")
      (libsource (lib "easyedapro") (part "Res"))
    )
    (comp (ref "R61")
      (value "20K")
      (footprint "easyedapro:R0201")
      (libsource (lib "easyedapro") (part "Res"))
    )
    (comp (ref "R62")
      (value "360K")
      (footprint "easyedapro:R0201")
      (libsource (lib "easyedapro") (part "Res"))
    )
    (comp (ref "R63")
      (value "348K")
      (footprint "easyedapro:R0201")
      (libsource (lib "easyedapro") (part "Res"))
    )
    (comp (ref "R64")
      (value "360K")
      (footprint "easyedapro:R0201")
      (libsource (lib "easyedapro") (part "Res"))
    )
    (comp (ref "R65")
      (value "115K")
      (footprint "easyedapro:R0201")
      (libsource (lib "easyedapro") (part "Res"))
    )
    (comp (ref "RJ1")
      (value "RB1-125B8G1A")
      (footprint "easyedapro:RJ45-TH_RB1-125B8G1A")
      (description "Connector Type:RJ45Receptacle Number of Ports:1 Shielding:- LED:WithLED Ratings:-")
      (fields (field (name "Manufacturer") "UDE(涌德电子)"))
      (libsource (lib "easyedapro") (part "RB1-125B8G1A"))
    )
    (comp (ref "RJ2")
      (value "RB1-125B8G1A")
      (footprint "easyedapro:RJ45-TH_RB1-125B8G1A")
      (description "Connector Type:RJ45Receptacle Number of Ports:1 Shielding:- LED:WithLED Ratings:-")
      (fields (field (name "Manufacturer") "UDE(涌德电子)"))
      (libsource (lib "easyedapro") (part "RB1-125B8G1A"))
    )
    (comp (ref "U5")
      (value "LAN7500I-ABZJ")
      (footprint "easyedapro:QFN-56_L8.0-W8.0-P0.50-BL-EP6.0")
      (fields (field (name "Manufacturer") "MICROCHIP(美国微芯)"))
      (libsource (lib "easyedapro") (part "LAN7500I-ABZJ"))
    )
    (comp (ref "U6")
      (value "STM6719SFWB6F")
      (footprint "easyedapro:SOT-23-6_L2.9-W1.6-P0.95-LS2.9-BL")
      (fields (field (name "Manufacturer") "ST(意法半导体)"))
      (libsource (lib "easyedapro") (part "STM6719SFWB6F"))
    )
    (comp (ref "U7")
      (value "TPS62410DRCR")
      (footprint "easyedapro:VSON-10_L3.0-W3.0-P0.50-BL-EP1.65")
      (fields (field (name "Manufacturer") "TI(德州仪器)"))
      (libsource (lib "easyedapro") (part "TPS62410DRCR"))
    )
    (comp (ref "U8")
      (value "LP5900SD-3.3/NOPB")
      (footprint "easyedapro:WSON-6_L2.0-W2.0-P0.65-BL-EP")
      (fields (field (name "Manufacturer") "TI(德州仪器)"))
      (libsource (lib "easyedapro") (part "LP5900SD-3.3/NOPB"))
    )
    (comp (ref "U9")
      (value "LAN7500I-ABZJ")
      (footprint "easyedapro:QFN-56_L8.0-W8.0-P0.50-BL-EP6.0")
      (fields (field (name "Manufacturer") "MICROCHIP(美国微芯)"))
      (libsource (lib "easyedapro") (part "LAN7500I-ABZJ"))
    )
    (comp (ref "U10")
      (value "STM6719SFWB6F")
      (footprint "easyedapro:SOT-23-6_L2.9-W1.6-P0.95-LS2.9-BL")
      (fields (field (name "Manufacturer") "ST(意法半导体)"))
      (libsource (lib "easyedapro") (part "STM6719SFWB6F"))
    )
    (comp (ref "U11")
      (value "TPS62410DRCR")
      (footprint "easyedapro:VSON-10_L3.0-W3.0-P0.50-BL-EP1.65")
      (fields (field (name "Manufacturer") "TI(德州仪器)"))
      (libsource (lib "easyedapro") (part "TPS62410DRCR"))
    )
    (comp (ref "U12")
      (value "LP5900SD-3.3/NOPB")
      (footprint "easyedapro:WSON-6_L2.0-W2.0-P0.65-BL-EP")
      (fields (field (name "Manufacturer") "TI(德州仪器)"))
      (libsource (lib "easyedapro") (part "LP5900SD-3.3/NOPB"))
    )
    (comp (ref "X1")
      (value "25MHz")
      (footprint "easyedapro:OSC-SMD_4P-L3.2-W2.5-BL")
      (fields (field (name "Manufacturer Part") "X322525MOB4SI") (field (name "Manufacturer") "YXC(扬兴晶振)"))
      (libsource (lib "easyedapro") (part "X322525MOB4SI"))
    )
    (comp (ref "X2")
      (value "25MHz")
      (footprint "easyedapro:OSC-SMD_4P-L3.2-W2.5-BL")
      (fields (field (name "Manufacturer Part") "X322525MOB4SI") (field (name "Manufacturer") "YXC(扬兴晶振)"))
      (libsource (lib "easyedapro") (part "X322525MOB4SI"))
    )
  )
  (nets
    (net (code "1") (name "+5V") (class "Default")
      (node (ref "C114") (pin "1") (pinfunction "1_1") (pintype "input"))
      (node (ref "C115") (pin "1") (pinfunction "1_1") (pintype "input"))
      (node (ref "C20") (pin "1") (pinfunction "1_1") (pintype "input"))
      (node (ref "C22") (pin "1") (pinfunction "1_1") (pintype "input"))
      (node (ref "C23") (pin "1") (pinfunction "1_1") (pintype "input"))
      (node (ref "C24") (pin "1") (pinfunction "1_1") (pintype "input"))
      (node (ref "C25") (pin "1") (pinfunction "1_1") (pintype "input"))
      (node (ref "C26") (pin "1") (pinfunction "1_1") (pintype "input"))
      (node (ref "C42") (pin "2") (pinfunction "2_2") (pintype "unspecified"))
      (node (ref "C46") (pin "1") (pinfunction "1_1") (pintype "input"))
      (node (ref "C74") (pin "2") (pinfunction "2_2") (pintype "unspecified"))
      (node (ref "C78") (pin "1") (pinfunction "1_1") (pintype "input"))
      (node (ref "CN2") (pin "57") (pinfunction "57_57") (pintype "input"))
      (node (ref "CN2") (pin "58") (pinfunction "58_58") (pintype "input"))
      (node (ref "CN2") (pin "59") (pinfunction "59_59") (pintype "input"))
      (node (ref "CN2") (pin "60") (pinfunction "60_60") (pintype "input"))
      (node (ref "CN2") (pin "61") (pinfunction "61_61") (pintype "input"))
      (node (ref "CN2") (pin "62") (pinfunction "62_62") (pintype "input"))
      (node (ref "D2") (pin "2") (pinfunction "+_2") (pintype "input"))
      (node (ref "D3") (pin "5") (pinfunction "5_5") (pintype "input"))
      (node (ref "F4") (pin "1") (pinfunction "1_1") (pintype "input"))
      (node (ref "R66") (pin "1") (pinfunction "1_1") (pintype "input"))
      (node (ref "U11") (pin "3") (pinfunction "VIN_3") (pintype "input"))
      (node (ref "U11") (pin "7") (pinfunction "EN1_7") (pintype "input"))
      (node (ref "U11") (pin "9") (pinfunction "EN2_9") (pintype "input"))
      (node (ref "U12") (pin "4") (pinfunction "EN_4") (pintype "unspecified"))
      (node (ref "U12") (pin "6") (pinfunction "IN_6") (pintype "unspecified"))
      (node (ref "U3") (pin "11") (pinfunction "VIN1_11") (pintype "unspecified"))
      (node (ref "U3") (pin "20") (pinfunction "VIN4_20") (pintype "unspecified"))
      (node (ref "U3") (pin "23") (pinfunction "VIN3_23") (pintype "unspecified"))
      (node (ref "U3") (pin "3") (pinfunction "VCC_3") (pintype "unspecified"))
      (node (ref "U3") (pin "8") (pinfunction "VIN2_8") (pintype "unspecified"))
      (node (ref "U7") (pin "3") (pinfunction "VIN_3") (pintype "input"))
      (node (ref "U7") (pin "7") (pinfunction "EN1_7") (pintype "input"))
      (node (ref "U7") (pin "9") (pinfunction "EN2_9") (pintype "input"))
      (node (ref "U8") (pin "4") (pinfunction "EN_4") (pintype "unspecified"))
      (node (ref "U8") (pin "6") (pinfunction "IN_6") (pintype "unspecified"))
    )
    (net (code "2") (name "+5V_HDMI") (class "Default")
      (node (ref "C12") (pin "1") (pinfunction "1_1") (pintype "input"))
      (node (ref "F6") (pin "2") (pinfunction "2_2") (pintype "input"))
      (node (ref "HDMI1") (pin "18") (pinfunction "+5VPower_18") (pintype "input"))
    )
    (net (code "3") (name "+5V_IN") (class "Default")
      (node (ref "C11") (pin "1") (pinfunction "1_1") (pintype "input"))
      (node (ref "F4") (pin "2") (pinfunction "2_2") (pintype "input"))
      (node (ref "USB1") (pin "A4") (pinfunction "VBUS_A4") (pintype "input"))
      (node (ref "USB1") (pin "A9") (pinfunction "VBUS_A9") (pintype "input"))
    )
    (net (code "4") (name "0V9") (class "Default")
      (node (ref "C107") (pin "1") (pinfunction "1_1") (pintype "input"))
      (node (ref "L19") (pin "1") (pinfunction "1_1") (pintype "unspecified"))
      (node (ref "R77") (pin "1") (pinfunction "1_1") (pintype "input"))
    )
    (net (code "5") (name "3V3") (class "Default")
      (node (ref "C29") (pin "1") (pinfunction "1_1") (pintype "input"))
      (node (ref "F7") (pin "2") (pinfunction "2_2") (pintype "input"))
      (node (ref "TF1") (pin "4") (pinfunction "VDD_4") (pintype "input"))
    )
    (net (code "6") (name "CAM_1V2") (class "Default")
      (node (ref "C106") (pin "1") (pinfunction "1_1") (pintype "input"))
      (node (ref "C112") (pin "1") (pinfunction "1_1") (pintype "input"))
      (node (ref "C113") (pin "1") (pinfunction "1_1") (pintype "input"))
      (node (ref "FPC1") (pin "27") (pinfunction "27_27") (pintype "input"))
      (node (ref "FPC1") (pin "28") (pinfunction "28_28") (pintype "input"))
      (node (ref "FPC2") (pin "27") (pinfunction "27_27") (pintype "input"))
      (node (ref "FPC2") (pin "28") (pinfunction "28_28") (pintype "input"))
      (node (ref "L1") (pin "1") (pinfunction "1_1") (pintype "unspecified"))
      (node (ref "R75") (pin "1") (pinfunction "1_1") (pintype "input"))
    )
    (net (code "7") (name "CAM_1V8") (class "Default")
      (node (ref "C105") (pin "1") (pinfunction "1_1") (pintype "input"))
      (node (ref "C108") (pin "1") (pinfunction "1_1") (pintype "input"))
      (node (ref "C109") (pin "1") (pinfunction "1_1") (pintype "input"))
      (node (ref "FPC1") (pin "30") (pinfunction "30_30") (pintype "input"))
      (node (ref "FPC2") (pin "30") (pinfunction "30_30") (pintype "input"))
      (node (ref "L18") (pin "1") (pinfunction "1_1") (pintype "unspecified"))
      (node (ref "R73") (pin "1") (pinfunction "1_1") (pintype "input"))
    )
    (net (code "8") (name "CAM_2V8") (class "Default")
      (node (ref "C104") (pin "1") (pinfunction "1_1") (pintype "input"))
      (node (ref "C110") (pin "1") (pinfunction "1_1") (pintype "input"))
      (node (ref "C111") (pin "1") (pinfunction "1_1") (pintype "input"))
      (node (ref "FPC1") (pin "24") (pinfunction "24_24") (pintype "input"))
      (node (ref "FPC1") (pin "25") (pinfunction "25_25") (pintype "input"))
      (node (ref "FPC2") (pin "24") (pinfunction "24_24") (pintype "input"))
      (node (ref "FPC2") (pin "25") (pinfunction "25_25") (pintype "input"))
      (node (ref "L17") (pin "1") (pinfunction "1_1") (pintype "unspecified"))
      (node (ref "R71") (pin "1") (pinfunction "1_1") (pintype "input"))
      (node (ref "R78") (pin "2") (pinfunction "2_2") (pintype "input"))
      (node (ref "R79") (pin "2") (pinfunction "2_2") (pintype "input"))
    )
    (net (code "9") (name "CAM_PWR_EN") (class "Default")
      (node (ref "C10") (pin "1") (pinfunction "1_1") (pintype "input"))
      (node (ref "R66") (pin "2") (pinfunction "2_2") (pintype "input"))
      (node (ref "R67") (pin "1") (pinfunction "1_1") (pintype "input"))
      (node (ref "U3") (pin "10") (pinfunction "EN1_10") (pintype "unspecified"))
      (node (ref "U3") (pin "21") (pinfunction "EN4_21") (pintype "unspecified"))
      (node (ref "U3") (pin "22") (pinfunction "EN3_22") (pintype "unspecified"))
      (node (ref "U3") (pin "9") (pinfunction "EN2_9") (pintype "unspecified"))
    )
    (net (code "10") (name "CM4_1V8") (class "Default")
      (node (ref "CN2") (pin "44") (pinfunction "44_44") (pintype "input"))
      (node (ref "CN2") (pin "45") (pinfunction "45_45") (pintype "input"))
    )
    (net (code "11") (name "CM4_3V3") (class "Default")
      (node (ref "C27") (pin "1") (pinfunction "1_1") (pintype "input"))
      (node (ref "C28") (pin "1") (pinfunction "1_1") (pintype "input"))
      (node (ref "CN2") (pin "39") (pinfunction "39_39") (pintype "input"))
      (node (ref "CN2") (pin "42") (pinfunction "42_42") (pintype "input"))
      (node (ref "CN2") (pin "43") (pinfunction "43_43") (pintype "input"))
      (node (ref "F7") (pin "1") (pinfunction "1_1") (pintype "input"))
    )
    (net (code "12") (name "CSI0_CKN") (class "Default")
      (node (ref "CN1") (pin "87") (pinfunction "87_87") (pintype "input"))
      (node (ref "FPC1") (pin "8") (pinfunction "8_8") (pintype "input"))
    )
    (net (code "13") (name "CSI0_CKP") (class "Default")
      (node (ref "CN1") (pin "86") (pinfunction "86_86") (pintype "input"))
      (node (ref "FPC1") (pin "9") (pinfunction "9_9") (pintype "input"))
    )
    (net (code "14") (name "CSI0_CLK") (class "Default")
      (node (ref "CN2") (pin "80") (pinfunction "80_80") (pintype "input"))
      (node (ref "FPC1") (pin "17") (pinfunction "17_17") (pintype "input"))
    )
    (net (code "15") (name "CSI0_D0N") (class "Default")
      (node (ref "CN1") (pin "93") (pinfunction "93_93") (pintype "input"))
      (node (ref "FPC1") (pin "5") (pinfunction "5_5") (pintype "input"))
    )
    (net (code "16") (name "CSI0_D0P") (class "Default")
      (node (ref "CN1") (pin "92") (pinfunction "92_92") (pintype "input"))
      (node (ref "FPC1") (pin "6") (pinfunction "6_6") (pintype "input"))
    )
    (net (code "17") (name "CSI0_D1N") (class "Default")
      (node (ref "CN1") (pin "90") (pinfunction "90_90") (pintype "input"))
      (node (ref "FPC1") (pin "11") (pinfunction "11_11") (pintype "input"))
    )
    (net (code "18") (name "CSI0_D1P") (class "Default")
      (node (ref "CN1") (pin "89") (pinfunction "89_89") (pintype "input"))
      (node (ref "FPC1") (pin "12") (pinfunction "12_12") (pintype "input"))
    )
    (net (code "19") (name "CSI0_D2N") (class "Default")
      (node (ref "CN1") (pin "84") (pinfunction "84_84") (pintype "input"))
      (node (ref "FPC1") (pin "2") (pinfunction "2_2") (pintype "input"))
    )
    (net (code "20") (name "CSI0_D2P") (class "Default")
      (node (ref "CN1") (pin "83") (pinfunction "83_83") (pintype "input"))
      (node (ref "FPC1") (pin "3") (pinfunction "3_3") (pintype "input"))
    )
    (net (code "21") (name "CSI0_D3N") (class "Default")
      (node (ref "CN1") (pin "81") (pinfunction "81_81") (pintype "input"))
      (node (ref "FPC1") (pin "14") (pinfunction "14_14") (pintype "input"))
    )
    (net (code "22") (name "CSI0_D3P") (class "Default")
      (node (ref "CN1") (pin "80") (pinfunction "80_80") (pintype "input"))
      (node (ref "FPC1") (pin "15") (pinfunction "15_15") (pintype "input"))
    )
    (net (code "23") (name "CSI0_NRST") (class "Default")
      (node (ref "FPC1") (pin "22") (pinfunction "22_22") (pintype "input"))
      (node (ref "R78") (pin "1") (pinfunction "1_1") (pintype "input"))
    )
    (net (code "24") (name "CSI1_CKN") (class "Default")
      (node (ref "CN1") (pin "20") (pinfunction "20_20") (pintype "input"))
      (node (ref "FPC2") (pin "8") (pinfunction "8_8") (pintype "input"))
    )
    (net (code "25") (name "CSI1_CKP") (class "Default")
      (node (ref "CN1") (pin "21") (pinfunction "21_21") (pintype "input"))
      (node (ref "FPC2") (pin "9") (pinfunction "9_9") (pintype "input"))
    )
    (net (code "26") (name "CSI1_CLK") (class "Default")
      (node (ref "CN2") (pin "29") (pinfunction "29_29") (pintype "input"))
      (node (ref "FPC2") (pin "17") (pinfunction "17_17") (pintype "input"))
    )
    (net (code "27") (name "CSI1_D0N") (class "Default")
      (node (ref "CN1") (pin "14") (pinfunction "14_14") (pintype "input"))
      (node (ref "FPC2") (pin "5") (pinfunction "5_5") (pintype "input"))
    )
    (net (code "28") (name "CSI1_D0P") (class "Default")
      (node (ref "CN1") (pin "15") (pinfunction "15_15") (pintype "input"))
      (node (ref "FPC2") (pin "6") (pinfunction "6_6") (pintype "input"))
    )
    (net (code "29") (name "CSI1_D1N") (class "Default")
      (node (ref "CN1") (pin "17") (pinfunction "17_17") (pintype "input"))
      (node (ref "FPC2") (pin "11") (pinfunction "11_11") (pintype "input"))
    )
    (net (code "30") (name "CSI1_D1P") (class "Default")
      (node (ref "CN1") (pin "18") (pinfunction "18_18") (pintype "input"))
      (node (ref "FPC2") (pin "12") (pinfunction "12_12") (pintype "input"))
    )
    (net (code "31") (name "CSI1_D2N") (class "Default")
      (node (ref "CN3") (pin "81") (pinfunction "81_81") (pintype "unspecified"))
      (node (ref "FPC2") (pin "2") (pinfunction "2_2") (pintype "input"))
    )
    (net (code "32") (name "CSI1_D2P") (class "Default")
      (node (ref "CN3") (pin "82") (pinfunction "82_82") (pintype "unspecified"))
      (node (ref "FPC2") (pin "3") (pinfunction "3_3") (pintype "input"))
    )
    (net (code "33") (name "CSI1_D3N") (class "Default")
      (node (ref "CN3") (pin "84") (pinfunction "84_84") (pintype "unspecified"))
      (node (ref "FPC2") (pin "14") (pinfunction "14_14") (pintype "input"))
    )
    (net (code "34") (name "CSI1_D3P") (class "Default")
      (node (ref "CN3") (pin "85") (pinfunction "85_85") (pintype "unspecified"))
      (node (ref "FPC2") (pin "15") (pinfunction "15_15") (pintype "input"))
    )
    (net (code "35") (name "CSI1_NRST") (class "Default")
      (node (ref "FPC2") (pin "22") (pinfunction "22_22") (pintype "input"))
      (node (ref "R79") (pin "1") (pinfunction "1_1") (pintype "input"))
    )
    (net (code "36") (name "EEPROM_NWP") (class "Default")
      (node (ref "H1") (pin "5") (pinfunction "5_5") (pintype "input"))
    )
    (net (code "37") (name "ETH0_1V2") (class "Default")
      (node (ref "C41") (pin "1") (pinfunction "1_1") (pintype "input"))
      (node (ref "C45") (pin "1") (pinfunction "1_1") (pintype "input"))
      (node (ref "C55") (pin "2") (pinfunction "2_2") (pintype "input"))
      (node (ref "C56") (pin "2") (pinfunction "2_2") (pintype "input"))
      (node (ref "C57") (pin "2") (pinfunction "2_2") (pintype "input"))
      (node (ref "C58") (pin "2") (pinfunction "2_2") (pintype "input"))
      (node (ref "C59") (pin "2") (pinfunction "2_2") (pintype "input"))
      (node (ref "C60") (pin "2") (pinfunction "2_2") (pintype "input"))
      (node (ref "C61") (pin "2") (pinfunction "2_2") (pintype "input"))
      (node (ref "C62") (pin "2") (pinfunction "2_2") (pintype "input"))
      (node (ref "L4") (pin "2") (pinfunction "2_2") (pintype "unspecified"))
      (node (ref "L7") (pin "1") (pinfunction "1_1") (pintype "input"))
      (node (ref "L8") (pin "1") (pinfunction "1_1") (pintype "input"))
      (node (ref "L9") (pin "1") (pinfunction "1_1") (pintype "input"))
      (node (ref "R39") (pin "2") (pinfunction "2_2") (pintype "input"))
      (node (ref "U5") (pin "11") (pinfunction "VDD12CORE_11") (pintype "unspecified"))
      (node (ref "U5") (pin "20") (pinfunction "VDD12CORE_20") (pintype "unspecified"))
      (node (ref "U5") (pin "23") (pinfunction "VDD12CORE_23") (pintype "unspecified"))
      (node (ref "U5") (pin "30") (pinfunction "VDD12CORE_30") (pintype "unspecified"))
      (node (ref "U5") (pin "36") (pinfunction "VDD12CORE_36") (pintype "unspecified"))
      (node (ref "U5") (pin "49") (pinfunction "VDD12BIAS_49") (pintype "unspecified"))
      (node (ref "U5") (pin "8") (pinfunction "VDD12CORE_8") (pintype "unspecified"))
      (node (ref "U6") (pin "4") (pinfunction "VCC2_4") (pintype "input"))
      (node (ref "U7") (pin "4") (pinfunction "FB1_4") (pintype "input"))
    )
    (net (code "38") (name "ETH0_1V2A") (class "Default")
      (node (ref "C63") (pin "2") (pinfunction "2_2") (pintype "input"))
      (node (ref "C64") (pin "2") (pinfunction "2_2") (pintype "input"))
      (node (ref "C65") (pin "2") (pinfunction "2_2") (pintype "input"))
      (node (ref "C66") (pin "2") (pinfunction "2_2") (pintype "input"))
      (node (ref "L9") (pin "2") (pinfunction "2_2") (pintype "input"))
      (node (ref "U5") (pin "45") (pinfunction "VDD12A_45") (pintype "unspecified"))
      (node (ref "U5") (pin "48") (pinfunction "VDD12A_48") (pintype "unspecified"))
      (node (ref "U5") (pin "53") (pinfunction "VDD12A_53") (pintype "unspecified"))
      (node (ref "U5") (pin "56") (pinfunction "VDD12A_56") (pintype "unspecified"))
    )
    (net (code "39") (name "ETH0_1V2PLL") (class "Default")
      (node (ref "C54") (pin "2") (pinfunction "2_2") (pintype "input"))
      (node (ref "L8") (pin "2") (pinfunction "2_2") (pintype "input"))
      (node (ref "U5") (pin "50") (pinfunction "VDD12PLL_50") (pintype "unspecified"))
    )
    (net (code "40") (name "ETH0_1V2USBPLL") (class "Default")
      (node (ref "C53") (pin "2") (pinfunction "2_2") (pintype "input"))
      (node (ref "L7") (pin "2") (pinfunction "2_2") (pintype "input"))
      (node (ref "U5") (pin "17") (pinfunction "VDD12USBPLL_17") (pintype "unspecified"))
    )
    (net (code "41") (name "ETH0_2V5") (class "Default")
      (node (ref "C43") (pin "1") (pinfunction "1_1") (pintype "input"))
      (node (ref "C44") (pin "1") (pinfunction "1_1") (pintype "input"))
      (node (ref "C49") (pin "2") (pinfunction "2_2") (pintype "input"))
      (node (ref "C50") (pin "2") (pinfunction "2_2") (pintype "input"))
      (node (ref "C51") (pin "2") (pinfunction "2_2") (pintype "input"))
      (node (ref "C52") (pin "2") (pinfunction "2_2") (pintype "input"))
      (node (ref "L3") (pin "1") (pinfunction "1_1") (pintype "input"))
      (node (ref "L5") (pin "2") (pinfunction "2_2") (pintype "unspecified"))
      (node (ref "R21") (pin "2") (pinfunction "2_2") (pintype "input"))
      (node (ref "R22") (pin "1") (pinfunction "1_1") (pintype "input"))
      (node (ref "R24") (pin "1") (pinfunction "1_1") (pintype "input"))
      (node (ref "R37") (pin "2") (pinfunction "2_2") (pintype "input"))
      (node (ref "R41") (pin "2") (pinfunction "2_2") (pintype "input"))
      (node (ref "U5") (pin "19") (pinfunction "VDDVARIO_19") (pintype "unspecified"))
      (node (ref "U5") (pin "24") (pinfunction "VDDVARIO_24") (pintype "unspecified"))
      (node (ref "U5") (pin "37") (pinfunction "VDDVARIO_37") (pintype "unspecified"))
      (node (ref "U5") (pin "7") (pinfunction "VDDVARIO_7") (pintype "unspecified"))
    )
    (net (code "42") (name "ETH0_2V5A_PHY") (class "Default")
      (node (ref "C30") (pin "2") (pinfunction "2_2") (pintype "input"))
      (node (ref "C31") (pin "2") (pinfunction "2_2") (pintype "input"))
      (node (ref "L3") (pin "2") (pinfunction "2_2") (pintype "input"))
      (node (ref "R26") (pin "2") (pinfunction "2_2") (pintype "input"))
      (node (ref "R27") (pin "2") (pinfunction "2_2") (pintype "input"))
      (node (ref "R28") (pin "2") (pinfunction "2_2") (pintype "input"))
      (node (ref "R29") (pin "2") (pinfunction "2_2") (pintype "input"))
      (node (ref "R30") (pin "2") (pinfunction "2_2") (pintype "input"))
      (node (ref "R31") (pin "2") (pinfunction "2_2") (pintype "input"))
      (node (ref "R32") (pin "2") (pinfunction "2_2") (pintype "input"))
      (node (ref "R33") (pin "2") (pinfunction "2_2") (pintype "input"))
      (node (ref "R36") (pin "2") (pinfunction "2_2") (pintype "input"))
      (node (ref "RJ1") (pin "L1") (pinfunction "LED1+_L1") (pintype "unspecified"))
      (node (ref "RJ1") (pin "L3") (pinfunction "LED2+_L3") (pintype "unspecified"))
    )
    (net (code "43") (name "ETH0_3V3") (class "Default")
      (node (ref "C40") (pin "1") (pinfunction "1_1") (pintype "input"))
      (node (ref "C47") (pin "1") (pinfunction "1_1") (pintype "input"))
      (node (ref "L6") (pin "1") (pinfunction "1_1") (pintype "input"))
      (node (ref "U6") (pin "6") (pinfunction "VCC1_6") (pintype "input"))
      (node (ref "U8") (pin "1") (pinfunction "OUT_1") (pintype "unspecified"))
    )
    (net (code "44") (name "ETH0_3V3A") (class "Default")
      (node (ref "C48") (pin "2") (pinfunction "2_2") (pintype "input"))
      (node (ref "L6") (pin "2") (pinfunction "2_2") (pintype "input"))
      (node (ref "U5") (pin "15") (pinfunction "VDD33A_15") (pintype "unspecified"))
    )
    (net (code "45") (name "ETH0_FECLK") (class "Default")
      (node (ref "U5") (pin "26") (pinfunction "EECLK_26") (pintype "unspecified"))
    )
    (net (code "46") (name "ETH0_FECS") (class "Default")
      (node (ref "U5") (pin "29") (pinfunction "EECS_29") (pintype "unspecified"))
    )
    (net (code "47") (name "ETH0_FEDI") (class "Default")
      (node (ref "U5") (pin "27") (pinfunction "EEDI_27") (pintype "unspecified"))
    )
    (net (code "48") (name "ETH0_FEDO") (class "Default")
      (node (ref "U5") (pin "28") (pinfunction "EEDO_28") (pintype "unspecified"))
    )
    (net (code "49") (name "ETH0_LED0") (class "Default")
      (node (ref "R35") (pin "1") (pinfunction "1_1") (pintype "input"))
      (node (ref "U5") (pin "31") (pinfunction "GPIO0/LED0_31") (pintype "unspecified"))
    )
    (net (code "50") (name "ETH0_LED1") (class "Default")
      (node (ref "R34") (pin "1") (pinfunction "1_1") (pintype "input"))
      (node (ref "U5") (pin "32") (pinfunction "GPIO1/LED1_32") (pintype "unspecified"))
    )
    (net (code "51") (name "ETH0_LED4") (class "Default")
      (node (ref "U5") (pin "35") (pinfunction "GPIO4/LED4_35") (pintype "unspecified"))
    )
    (net (code "52") (name "ETH0_NRST") (class "Default")
      (node (ref "R21") (pin "1") (pinfunction "1_1") (pintype "input"))
      (node (ref "U5") (pin "42") (pinfunction "NRESET/PME_CLEAR_42") (pintype "unspecified"))
      (node (ref "U6") (pin "1") (pinfunction "RST#_1") (pintype "input"))
    )
    (net (code "53") (name "ETH0_SWMODE_R") (class "Default")
      (node (ref "R23") (pin "1") (pinfunction "1_1") (pintype "input"))
    )
    (net (code "54") (name "ETH0_TR0_N") (class "Default")
      (node (ref "R33") (pin "1") (pinfunction "1_1") (pintype "input"))
      (node (ref "RJ1") (pin "R2") (pinfunction "TD1+_R2") (pintype "unspecified"))
      (node (ref "U5") (pin "43") (pinfunction "TR0N_43") (pintype "unspecified"))
    )
    (net (code "55") (name "ETH0_TR0_P") (class "Default")
      (node (ref "R32") (pin "1") (pinfunction "1_1") (pintype "input"))
      (node (ref "RJ1") (pin "R3") (pinfunction "TD1-_R3") (pintype "unspecified"))
      (node (ref "U5") (pin "44") (pinfunction "TR0P_44") (pintype "unspecified"))
    )
    (net (code "56") (name "ETH0_TR1_N") (class "Default")
      (node (ref "R31") (pin "1") (pinfunction "1_1") (pintype "input"))
      (node (ref "RJ1") (pin "R4") (pinfunction "TD2+_R4") (pintype "unspecified"))
      (node (ref "U5") (pin "46") (pinfunction "TR1N_46") (pintype "unspecified"))
    )
    (net (code "57") (name "ETH0_TR1_P") (class "Default")
      (node (ref "R30") (pin "1") (pinfunction "1_1") (pintype "input"))
      (node (ref "RJ1") (pin "R5") (pinfunction "TD2-_R5") (pintype "unspecified"))
      (node (ref "U5") (pin "47") (pinfunction "TR1P_47") (pintype "unspecified"))
    )
    (net (code "58") (name "ETH0_TR2_N") (class "Default")
      (node (ref "R29") (pin "1") (pinfunction "1_1") (pintype "input"))
      (node (ref "RJ1") (pin "R6") (pinfunction "TD3+_R6") (pintype "unspecified"))
      (node (ref "U5") (pin "51") (pinfunction "TR2N_51") (pintype "unspecified"))
    )
    (net (code "59") (name "ETH0_TR2_P") (class "Default")
      (node (ref "R28") (pin "1") (pinfunction "1_1") (pintype "input"))
      (node (ref "RJ1") (pin "R7") (pinfunction "TD3-_R7") (pintype "unspecified"))
      (node (ref "U5") (pin "52") (pinfunction "TR2P_52") (pintype "unspecified"))
    )
    (net (code "60") (name "ETH0_TR3_N") (class "Default")
      (node (ref "R27") (pin "1") (pinfunction "1_1") (pintype "input"))
      (node (ref "RJ1") (pin "R8") (pinfunction "TD4+_R8") (pintype "unspecified"))
      (node (ref "U5") (pin "54") (pinfunction "TR3N_54") (pintype "unspecified"))
    )
    (net (code "61") (name "ETH0_TR3_P") (class "Default")
      (node (ref "R26") (pin "1") (pinfunction "1_1") (pintype "input"))
      (node (ref "RJ1") (pin "R9") (pinfunction "TD4-_R9") (pintype "unspecified"))
      (node (ref "U5") (pin "55") (pinfunction "TR3P_55") (pintype "unspecified"))
    )
    (net (code "62") (name "ETH0_USB_M") (class "Default")
      (node (ref "CN3") (pin "93") (pinfunction "93_93") (pintype "unspecified"))
      (node (ref "U5") (pin "12") (pinfunction "USBDM_12") (pintype "unspecified"))
    )
    (net (code "63") (name "ETH0_USB_P") (class "Default")
      (node (ref "CN3") (pin "94") (pinfunction "94_94") (pintype "unspecified"))
      (node (ref "U5") (pin "13") (pinfunction "USBDP_13") (pintype "unspecified"))
    )
    (net (code "64") (name "ETH1_1V2") (class "Default")
      (node (ref "C73") (pin "1") (pinfunction "1_1") (pintype "input"))
      (node (ref "C77") (pin "1") (pinfunction "1_1") (pintype "input"))
      (node (ref "C88") (pin "2") (pinfunction "2_2") (pintype "input"))
      (node (ref "C89") (pin "2") (pinfunction "2_2") (pintype "input"))
      (node (ref "C90") (pin "2") (pinfunction "2_2") (pintype "input"))
      (node (ref "C91") (pin "2") (pinfunction "2_2") (pintype "input"))
      (node (ref "C92") (pin "2") (pinfunction "2_2") (pintype "input"))
      (node (ref "C93") (pin "2") (pinfunction "2_2") (pintype "input"))
      (node (ref "C94") (pin "2") (pinfunction "2_2") (pintype "input"))
      (node (ref "C95") (pin "2") (pinfunction "2_2") (pintype "input"))
      (node (ref "L10") (pin "2") (pinfunction "2_2") (pintype "unspecified"))
      (node (ref "L14") (pin "1") (pinfunction "1_1") (pintype "input"))
      (node (ref "L15") (pin "1") (pinfunction "1_1") (pintype "input"))
      (node (ref "L16") (pin "1") (pinfunction "1_1") (pintype "input"))
      (node (ref "R62") (pin "2") (pinfunction "2_2") (pintype "input"))
      (node (ref "U10") (pin "4") (pinfunction "VCC2_4") (pintype "input"))
      (node (ref "U11") (pin "4") (pinfunction "FB1_4") (pintype "input"))
      (node (ref "U9") (pin "11") (pinfunction "VDD12CORE_11") (pintype "unspecified"))
      (node (ref "U9") (pin "20") (pinfunction "VDD12CORE_20") (pintype "unspecified"))
      (node (ref "U9") (pin "23") (pinfunction "VDD12CORE_23") (pintype "unspecified"))
      (node (ref "U9") (pin "30") (pinfunction "VDD12CORE_30") (pintype "unspecified"))
      (node (ref "U9") (pin "36") (pinfunction "VDD12CORE_36") (pintype "unspecified"))
      (node (ref "U9") (pin "49") (pinfunction "VDD12BIAS_49") (pintype "unspecified"))
      (node (ref "U9") (pin "8") (pinfunction "VDD12CORE_8") (pintype "unspecified"))
    )
    (net (code "65") (name "ETH1_1V2A") (class "Default")
      (node (ref "C96") (pin "2") (pinfunction "2_2") (pintype "input"))
      (node (ref "C97") (pin "2") (pinfunction "2_2") (pintype "input"))
      (node (ref "C98") (pin "2") (pinfunction "2_2") (pintype "input"))
      (node (ref "C99") (pin "2") (pinfunction "2_2") (pintype "input"))
      (node (ref "L16") (pin "2") (pinfunction "2_2") (pintype "input"))
      (node (ref "U9") (pin "45") (pinfunction "VDD12A_45") (pintype "unspecified"))
      (node (ref "U9") (pin "48") (pinfunction "VDD12A_48") (pintype "unspecified"))
      (node (ref "U9") (pin "53") (pinfunction "VDD12A_53") (pintype "unspecified"))
      (node (ref "U9") (pin "56") (pinfunction "VDD12A_56") (pintype "unspecified"))
    )
    (net (code "66") (name "ETH1_1V2PLL") (class "Default")
      (node (ref "C87") (pin "2") (pinfunction "2_2") (pintype "input"))
      (node (ref "L15") (pin "2") (pinfunction "2_2") (pintype "input"))
      (node (ref "U9") (pin "50") (pinfunction "VDD12PLL_50") (pintype "unspecified"))
    )
    (net (code "67") (name "ETH1_1V2USBPLL") (class "Default")
      (node (ref "C86") (pin "2") (pinfunction "2_2") (pintype "input"))
      (node (ref "L14") (pin "2") (pinfunction "2_2") (pintype "input"))
      (node (ref "U9") (pin "17") (pinfunction "VDD12USBPLL_17") (pintype "unspecified"))
    )
    (net (code "68") (name "ETH1_2V5") (class "Default")
      (node (ref "C75") (pin "1") (pinfunction "1_1") (pintype "input"))
      (node (ref "C76") (pin "1") (pinfunction "1_1") (pintype "input"))
      (node (ref "C82") (pin "2") (pinfunction "2_2") (pintype "input"))
      (node (ref "C83") (pin "2") (pinfunction "2_2") (pintype "input"))
      (node (ref "C84") (pin "2") (pinfunction "2_2") (pintype "input"))
      (node (ref "C85") (pin "2") (pinfunction "2_2") (pintype "input"))
      (node (ref "L11") (pin "2") (pinfunction "2_2") (pintype "unspecified"))
      (node (ref "L12") (pin "1") (pinfunction "1_1") (pintype "input"))
      (node (ref "R44") (pin "2") (pinfunction "2_2") (pintype "input"))
      (node (ref "R45") (pin "1") (pinfunction "1_1") (pintype "input"))
      (node (ref "R47") (pin "1") (pinfunction "1_1") (pintype "input"))
      (node (ref "R60") (pin "2") (pinfunction "2_2") (pintype "input"))
      (node (ref "R64") (pin "2") (pinfunction "2_2") (pintype "input"))
      (node (ref "U9") (pin "19") (pinfunction "VDDVARIO_19") (pintype "unspecified"))
      (node (ref "U9") (pin "24") (pinfunction "VDDVARIO_24") (pintype "unspecified"))
      (node (ref "U9") (pin "37") (pinfunction "VDDVARIO_37") (pintype "unspecified"))
      (node (ref "U9") (pin "7") (pinfunction "VDDVARIO_7") (pintype "unspecified"))
    )
    (net (code "69") (name "ETH1_2V5A_PHY") (class "Default")
      (node (ref "C69") (pin "2") (pinfunction "2_2") (pintype "input"))
      (node (ref "C80") (pin "2") (pinfunction "2_2") (pintype "input"))
      (node (ref "L12") (pin "2") (pinfunction "2_2") (pintype "input"))
      (node (ref "R49") (pin "2") (pinfunction "2_2") (pintype "input"))
      (node (ref "R50") (pin "2") (pinfunction "2_2") (pintype "input"))
      (node (ref "R51") (pin "2") (pinfunction "2_2") (pintype "input"))
      (node (ref "R52") (pin "2") (pinfunction "2_2") (pintype "input"))
      (node (ref "R53") (pin "2") (pinfunction "2_2") (pintype "input"))
      (node (ref "R54") (pin "2") (pinfunction "2_2") (pintype "input"))
      (node (ref "R55") (pin "2") (pinfunction "2_2") (pintype "input"))
      (node (ref "R56") (pin "2") (pinfunction "2_2") (pintype "input"))
      (node (ref "R59") (pin "2") (pinfunction "2_2") (pintype "input"))
      (node (ref "RJ2") (pin "L1") (pinfunction "LED1+_L1") (pintype "unspecified"))
      (node (ref "RJ2") (pin "L3") (pinfunction "LED2+_L3") (pintype "unspecified"))
    )
    (net (code "70") (name "ETH1_3V3") (class "Default")
      (node (ref "C72") (pin "1") (pinfunction "1_1") (pintype "input"))
      (node (ref "C79") (pin "1") (pinfunction "1_1") (pintype "input"))
      (node (ref "L13") (pin "1") (pinfunction "1_1") (pintype "input"))
      (node (ref "U10") (pin "6") (pinfunction "VCC1_6") (pintype "input"))
      (node (ref "U12") (pin "1") (pinfunction "OUT_1") (pintype "unspecified"))
    )
    (net (code "71") (name "ETH1_3V3A") (class "Default")
      (node (ref "C81") (pin "2") (pinfunction "2_2") (pintype "input"))
      (node (ref "L13") (pin "2") (pinfunction "2_2") (pintype "input"))
      (node (ref "U9") (pin "15") (pinfunction "VDD33A_15") (pintype "unspecified"))
    )
    (net (code "72") (name "ETH1_FECLK") (class "Default")
      (node (ref "U9") (pin "26") (pinfunction "EECLK_26") (pintype "unspecified"))
    )
    (net (code "73") (name "ETH1_FECS") (class "Default")
      (node (ref "U9") (pin "29") (pinfunction "EECS_29") (pintype "unspecified"))
    )
    (net (code "74") (name "ETH1_FEDI") (class "Default")
      (node (ref "U9") (pin "27") (pinfunction "EEDI_27") (pintype "unspecified"))
    )
    (net (code "75") (name "ETH1_FEDO") (class "Default")
      (node (ref "U9") (pin "28") (pinfunction "EEDO_28") (pintype "unspecified"))
    )
    (net (code "76") (name "ETH1_LED0") (class "Default")
      (node (ref "R58") (pin "1") (pinfunction "1_1") (pintype "input"))
      (node (ref "U9") (pin "31") (pinfunction "GPIO0/LED0_31") (pintype "unspecified"))
    )
    (net (code "77") (name "ETH1_LED1") (class "Default")
      (node (ref "R57") (pin "1") (pinfunction "1_1") (pintype "input"))
      (node (ref "U9") (pin "32") (pinfunction "GPIO1/LED1_32") (pintype "unspecified"))
    )
    (net (code "78") (name "ETH1_LED4") (class "Default")
      (node (ref "U9") (pin "35") (pinfunction "GPIO4/LED4_35") (pintype "unspecified"))
    )
    (net (code "79") (name "ETH1_NRST") (class "Default")
      (node (ref "R44") (pin "1") (pinfunction "1_1") (pintype "input"))
      (node (ref "U10") (pin "1") (pinfunction "RST#_1") (pintype "input"))
      (node (ref "U9") (pin "42") (pinfunction "NRESET/PME_CLEAR_42") (pintype "unspecified"))
    )
    (net (code "80") (name "ETH1_SWMODE_R") (class "Default")
      (node (ref "R46") (pin "1") (pinfunction "1_1") (pintype "input"))
    )
    (net (code "81") (name "ETH1_TR0_N") (class "Default")
      (node (ref "R56") (pin "1") (pinfunction "1_1") (pintype "input"))
      (node (ref "RJ2") (pin "R2") (pinfunction "TD1+_R2") (pintype "unspecified"))
      (node (ref "U9") (pin "43") (pinfunction "TR0N_43") (pintype "unspecified"))
    )
    (net (code "82") (name "ETH1_TR0_P") (class "Default")
      (node (ref "R55") (pin "1") (pinfunction "1_1") (pintype "input"))
      (node (ref "RJ2") (pin "R3") (pinfunction "TD1-_R3") (pintype "unspecified"))
      (node (ref "U9") (pin "44") (pinfunction "TR0P_44") (pintype "unspecified"))
    )
    (net (code "83") (name "ETH1_TR1_N") (class "Default")
      (node (ref "R54") (pin "1") (pinfunction "1_1") (pintype "input"))
      (node (ref "RJ2") (pin "R4") (pinfunction "TD2+_R4") (pintype "unspecified"))
      (node (ref "U9") (pin "46") (pinfunction "TR1N_46") (pintype "unspecified"))
    )
    (net (code "84") (name "ETH1_TR1_P") (class "Default")
      (node (ref "R53") (pin "1") (pinfunction "1_1") (pintype "input"))
      (node (ref "RJ2") (pin "R5") (pinfunction "TD2-_R5") (pintype "unspecified"))
      (node (ref "U9") (pin "47") (pinfunction "TR1P_47") (pintype "unspecified"))
    )
    (net (code "85") (name "ETH1_TR2_N") (class "Default")
      (node (ref "R52") (pin "1") (pinfunction "1_1") (pintype "input"))
      (node (ref "RJ2") (pin "R6") (pinfunction "TD3+_R6") (pintype "unspecified"))
      (node (ref "U9") (pin "51") (pinfunction "TR2N_51") (pintype "unspecified"))
    )
    (net (code "86") (name "ETH1_TR2_P") (class "Default")
      (node (ref "R51") (pin "1") (pinfunction "1_1") (pintype "input"))
      (node (ref "RJ2") (pin "R7") (pinfunction "TD3-_R7") (pintype "unspecified"))
      (node (ref "U9") (pin "52") (pinfunction "TR2P_52") (pintype "unspecified"))
    )
    (net (code "87") (name "ETH1_TR3_N") (class "Default")
      (node (ref "R50") (pin "1") (pinfunction "1_1") (pintype "input"))
      (node (ref "RJ2") (pin "R8") (pinfunction "TD4+_R8") (pintype "unspecified"))
      (node (ref "U9") (pin "54") (pinfunction "TR3N_54") (pintype "unspecified"))
    )
    (net (code "88") (name "ETH1_TR3_P") (class "Default")
      (node (ref "R49") (pin "1") (pinfunction "1_1") (pintype "input"))
      (node (ref "RJ2") (pin "R9") (pinfunction "TD4-_R9") (pintype "unspecified"))
      (node (ref "U9") (pin "55") (pinfunction "TR3P_55") (pintype "unspecified"))
    )
    (net (code "89") (name "ETH1_USB_M") (class "Default")
      (node (ref "CN3") (pin "99") (pinfunction "99_99") (pintype "unspecified"))
      (node (ref "U9") (pin "12") (pinfunction "USBDM_12") (pintype "unspecified"))
    )
    (net (code "90") (name "ETH1_USB_P") (class "Default")
      (node (ref "CN3") (pin "100") (pinfunction "100_100") (pintype "unspecified"))
      (node (ref "U9") (pin "13") (pinfunction "USBDP_13") (pintype "unspecified"))
    )
    (net (code "91") (name "GLOBAL_EN") (class "Default")
      (node (ref "CN2") (pin "51") (pinfunction "51_51") (pintype "input"))
      (node (ref "H1") (pin "1") (pinfunction "1_1") (pintype "input"))
    )
    (net (code "92") (name "GND") (class "Default")
      (node (ref "C10") (pin "2") (pinfunction "2_2") (pintype "input"))
      (node (ref "C100") (pin "2") (pinfunction "2_2") (pintype "input"))
      (node (ref "C101") (pin "1") (pinfunction "1_1") (pintype "input"))
      (node (ref "C104") (pin "2") (pinfunction "2_2") (pintype "input"))
      (node (ref "C105") (pin "2") (pinfunction "2_2") (pintype "input"))
      (node (ref "C106") (pin "2") (pinfunction "2_2") (pintype "input"))
      (node (ref "C107") (pin "2") (pinfunction "2_2") (pintype "input"))
      (node (ref "C108") (pin "2") (pinfunction "2_2") (pintype "input"))
      (node (ref "C109") (pin "2") (pinfunction "2_2") (pintype "input"))
      (node (ref "C11") (pin "2") (pinfunction "2_2") (pintype "input"))
      (node (ref "C110") (pin "2") (pinfunction "2_2") (pintype "input"))
      (node (ref "C111") (pin "2") (pinfunction "2_2") (pintype "input"))
      (node (ref "C112") (pin "2") (pinfunction "2_2") (pintype "input"))
      (node (ref "C113") (pin "2") (pinfunction "2_2") (pintype "input"))
      (node (ref "C114") (pin "2") (pinfunction "2_2") (pintype "input"))
      (node (ref "C115") (pin "2") (pinfunction "2_2") (pintype "input"))
      (node (ref "C12") (pin "2") (pinfunction "2_2") (pintype "input"))
      (node (ref "C20") (pin "2") (pinfunction "2_2") (pintype "input"))
      (node (ref "C22") (pin "2") (pinfunction "2_2") (pintype "input"))
      (node (ref "C23") (pin "2") (pinfunction "2_2") (pintype "input"))
      (node (ref "C24") (pin "2") (pinfunction "2_2") (pintype "input"))
      (node (ref "C25") (pin "2") (pinfunction "2_2") (pintype "input"))
      (node (ref "C26") (pin "2") (pinfunction "2_2") (pintype "input"))
      (node (ref "C27") (pin "2") (pinfunction "2_2") (pintype "input"))
      (node (ref "C28") (pin "2") (pinfunction "2_2") (pintype "input"))
      (node (ref "C29") (pin "2") (pinfunction "2_2") (pintype "input"))
      (node (ref "C30") (pin "1") (pinfunction "1_1") (pintype "input"))
      (node (ref "C31") (pin "1") (pinfunction "1_1") (pintype "input"))
      (node (ref "C38") (pin "2") (pinfunction "2_2") (pintype "input"))
      (node (ref "C39") (pin "1") (pinfunction "1_1") (pintype "input"))
      (node (ref "C40") (pin "2") (pinfunction "2_2") (pintype "input"))
      (node (ref "C41") (pin "2") (pinfunction "2_2") (pintype "input"))
      (node (ref "C42") (pin "1") (pinfunction "1_1") (pintype "unspecified"))
      (node (ref "C44") (pin "2") (pinfunction "2_2") (pintype "input"))
      (node (ref "C45") (pin "2") (pinfunction "2_2") (pintype "input"))
      (node (ref "C46") (pin "2") (pinfunction "2_2") (pintype "input"))
      (node (ref "C47") (pin "2") (pinfunction "2_2") (pintype "input"))
      (node (ref "C48") (pin "1") (pinfunction "1_1") (pintype "input"))
      (node (ref "C49") (pin "1") (pinfunction "1_1") (pintype "input"))
      (node (ref "C50") (pin "1") (pinfunction "1_1") (pintype "input"))
      (node (ref "C51") (pin "1") (pinfunction "1_1") (pintype "input"))
      (node (ref "C52") (pin "1") (pinfunction "1_1") (pintype "input"))
      (node (ref "C53") (pin "1") (pinfunction "1_1") (pintype "input"))
      (node (ref "C54") (pin "1") (pinfunction "1_1") (pintype "input"))
      (node (ref "C55") (pin "1") (pinfunction "1_1") (pintype "input"))
      (node (ref "C56") (pin "1") (pinfunction "1_1") (pintype "input"))
      (node (ref "C57") (pin "1") (pinfunction "1_1") (pintype "input"))
      (node (ref "C58") (pin "1") (pinfunction "1_1") (pintype "input"))
      (node (ref "C59") (pin "1") (pinfunction "1_1") (pintype "input"))
      (node (ref "C60") (pin "1") (pinfunction "1_1") (pintype "input"))
      (node (ref "C61") (pin "1") (pinfunction "1_1") (pintype "input"))
      (node (ref "C62") (pin "1") (pinfunction "1_1") (pintype "input"))
      (node (ref "C63") (pin "1") (pinfunction "1_1") (pintype "input"))
      (node (ref "C64") (pin "1") (pinfunction "1_1") (pintype "input"))
      (node (ref "C65") (pin "1") (pinfunction "1_1") (pintype "input"))
      (node (ref "C66") (pin "1") (pinfunction "1_1") (pintype "input"))
      (node (ref "C67") (pin "2") (pinfunction "2_2") (pintype "input"))
      (node (ref "C68") (pin "1") (pinfunction "1_1") (pintype "input"))
      (node (ref "C69") (pin "1") (pinfunction "1_1") (pintype "input"))
      (node (ref "C70") (pin "2") (pinfunction "2_2") (pintype "input"))
      (node (ref "C71") (pin "1") (pinfunction "1_1") (pintype "input"))
      (node (ref "C72") (pin "2") (pinfunction "2_2") (pintype "input"))
      (node (ref "C73") (pin "2") (pinfunction "2_2") (pintype "input"))
      (node (ref "C74") (pin "1") (pinfunction "1_1") (pintype "unspecified"))
      (node (ref "C76") (pin "2") (pinfunction "2_2") (pintype "input"))
      (node (ref "C77") (pin "2") (pinfunction "2_2") (pintype "input"))
      (node (ref "C78") (pin "2") (pinfunction "2_2") (pintype "input"))
      (node (ref "C79") (pin "2") (pinfunction "2_2") (pintype "input"))
      (node (ref "C80") (pin "1") (pinfunction "1_1") (pintype "input"))
      (node (ref "C81") (pin "1") (pinfunction "1_1") (pintype "input"))
      (node (ref "C82") (pin "1") (pinfunction "1_1") (pintype "input"))
      (node (ref "C83") (pin "1") (pinfunction "1_1") (pintype "input"))
      (node (ref "C84") (pin "1") (pinfunction "1_1") (pintype "input"))
      (node (ref "C85") (pin "1") (pinfunction "1_1") (pintype "input"))
      (node (ref "C86") (pin "1") (pinfunction "1_1") (pintype "input"))
      (node (ref "C87") (pin "1") (pinfunction "1_1") (pintype "input"))
      (node (ref "C88") (pin "1") (pinfunction "1_1") (pintype "input"))
      (node (ref "C89") (pin "1") (pinfunction "1_1") (pintype "input"))
      (node (ref "C90") (pin "1") (pinfunction "1_1") (pintype "input"))
      (node (ref "C91") (pin "1") (pinfunction "1_1") (pintype "input"))
      (node (ref "C92") (pin "1") (pinfunction "1_1") (pintype "input"))
      (node (ref "C93") (pin "1") (pinfunction "1_1") (pintype "input"))
      (node (ref "C94") (pin "1") (pinfunction "1_1") (pintype "input"))
      (node (ref "C95") (pin "1") (pinfunction "1_1") (pintype "input"))
      (node (ref "C96") (pin "1") (pinfunction "1_1") (pintype "input"))
      (node (ref "C97") (pin "1") (pinfunction "1_1") (pintype "input"))
      (node (ref "C98") (pin "1") (pinfunction "1_1") (pintype "input"))
      (node (ref "C99") (pin "1") (pinfunction "1_1") (pintype "input"))
      (node (ref "CN1") (pin "10") (pinfunction "10_10") (pintype "input"))
      (node (ref "CN1") (pin "13") (pinfunction "13_13") (pintype "input"))
      (node (ref "CN1") (pin "16") (pinfunction "16_16") (pintype "input"))
      (node (ref "CN1") (pin "19") (pinfunction "19_19") (pintype "input"))
      (node (ref "CN1") (pin "22") (pinfunction "22_22") (pintype "input"))
      (node (ref "CN1") (pin "25") (pinfunction "25_25") (pintype "input"))
      (node (ref "CN1") (pin "28") (pinfunction "28_28") (pintype "input"))
      (node (ref "CN1") (pin "31") (pinfunction "31_31") (pintype "input"))
      (node (ref "CN1") (pin "34") (pinfunction "34_34") (pintype "input"))
      (node (ref "CN1") (pin "37") (pinfunction "37_37") (pintype "input"))
      (node (ref "CN1") (pin "4") (pinfunction "4_4") (pintype "input"))
      (node (ref "CN1") (pin "40") (pinfunction "40_40") (pintype "input"))
      (node (ref "CN1") (pin "43") (pinfunction "43_43") (pintype "input"))
      (node (ref "CN1") (pin "46") (pinfunction "46_46") (pintype "input"))
      (node (ref "CN1") (pin "49") (pinfunction "49_49") (pintype "input"))
      (node (ref "CN1") (pin "52") (pinfunction "52_52") (pintype "input"))
      (node (ref "CN1") (pin "55") (pinfunction "55_55") (pintype "input"))
      (node (ref "CN1") (pin "58") (pinfunction "58_58") (pintype "input"))
      (node (ref "CN1") (pin "61") (pinfunction "61_61") (pintype "input"))
      (node (ref "CN1") (pin "64") (pinfunction "64_64") (pintype "input"))
      (node (ref "CN1") (pin "67") (pinfunction "67_67") (pintype "input"))
      (node (ref "CN1") (pin "7") (pinfunction "7_7") (pintype "input"))
      (node (ref "CN1") (pin "70") (pinfunction "70_70") (pintype "input"))
      (node (ref "CN1") (pin "73") (pinfunction "73_73") (pintype "input"))
      (node (ref "CN1") (pin "82") (pinfunction "82_82") (pintype "input"))
      (node (ref "CN1") (pin "85") (pinfunction "85_85") (pintype "input"))
      (node (ref "CN1") (pin "88") (pinfunction "88_88") (pintype "input"))
      (node (ref "CN1") (pin "91") (pinfunction "91_91") (pintype "input"))
      (node (ref "CN1") (pin "94") (pinfunction "94_94") (pintype "input"))
      (node (ref "CN1") (pin "97") (pinfunction "97_97") (pintype "input"))
      (node (ref "CN2") (pin "1") (pinfunction "1_1") (pintype "input"))
      (node (ref "CN2") (pin "100") (pinfunction "100_100") (pintype "input"))
      (node (ref "CN2") (pin "11") (pinfunction "11_11") (pintype "input"))
      (node (ref "CN2") (pin "16") (pinfunction "16_16") (pintype "input"))
      (node (ref "CN2") (pin "21") (pinfunction "21_21") (pintype "input"))
      (node (ref "CN2") (pin "26") (pinfunction "26_26") (pintype "input"))
      (node (ref "CN2") (pin "30") (pinfunction "30_30") (pintype "input"))
      (node (ref "CN2") (pin "33") (pinfunction "33_33") (pintype "input"))
      (node (ref "CN2") (pin "37") (pinfunction "37_37") (pintype "input"))
      (node (ref "CN2") (pin "4") (pinfunction "4_4") (pintype "input"))
      (node (ref "CN2") (pin "49") (pinfunction "49_49") (pintype "input"))
      (node (ref "CN2") (pin "65") (pinfunction "65_65") (pintype "input"))
      (node (ref "CN2") (pin "68") (pinfunction "68_68") (pintype "input"))
      (node (ref "CN2") (pin "7") (pinfunction "7_7") (pintype "input"))
      (node (ref "CN2") (pin "71") (pinfunction "71_71") (pintype "input"))
      (node (ref "CN2") (pin "74") (pinfunction "74_74") (pintype "input"))
      (node (ref "CN2") (pin "79") (pinfunction "79_79") (pintype "input"))
      (node (ref "CN2") (pin "84") (pinfunction "84_84") (pintype "input"))
      (node (ref "CN2") (pin "89") (pinfunction "89_89") (pintype "input"))
      (node (ref "CN2") (pin "94") (pinfunction "94_94") (pintype "input"))
      (node (ref "CN2") (pin "97") (pinfunction "97_97") (pintype "input"))
      (node (ref "CN3") (pin "16") (pinfunction "16_16") (pintype "unspecified"))
      (node (ref "CN3") (pin "22") (pinfunction "22_22") (pintype "unspecified"))
      (node (ref "CN3") (pin "27") (pinfunction "27_27") (pintype "unspecified"))
      (node (ref "CN3") (pin "3") (pinfunction "3_3") (pintype "unspecified"))
      (node (ref "CN3") (pin "32") (pinfunction "32_32") (pintype "unspecified"))
      (node (ref "CN3") (pin "37") (pinfunction "37_37") (pintype "unspecified"))
      (node (ref "CN3") (pin "40") (pinfunction "40_40") (pintype "unspecified"))
      (node (ref "CN3") (pin "43") (pinfunction "43_43") (pintype "unspecified"))
      (node (ref "CN3") (pin "46") (pinfunction "46_46") (pintype "unspecified"))
      (node (ref "CN3") (pin "50") (pinfunction "50_50") (pintype "unspecified"))
      (node (ref "CN3") (pin "51") (pinfunction "51_51") (pintype "unspecified"))
      (node (ref "CN3") (pin "57") (pinfunction "57_57") (pintype "unspecified"))
      (node (ref "CN3") (pin "6") (pinfunction "6_6") (pintype "unspecified"))
      (node (ref "CN3") (pin "63") (pinfunction "63_63") (pintype "unspecified"))
      (node (ref "CN3") (pin "68") (pinfunction "68_68") (pintype "unspecified"))
      (node (ref "CN3") (pin "73") (pinfunction "73_73") (pintype "unspecified"))
      (node (ref "CN3") (pin "78") (pinfunction "78_78") (pintype "unspecified"))
      (node (ref "CN3") (pin "80") (pinfunction "80_80") (pintype "unspecified"))
      (node (ref "CN3") (pin "83") (pinfunction "83_83") (pintype "unspecified"))
      (node (ref "CN3") (pin "86") (pinfunction "86_86") (pintype "unspecified"))
      (node (ref "CN3") (pin "89") (pinfunction "89_89") (pintype "unspecified"))
      (node (ref "CN3") (pin "9") (pinfunction "9_9") (pintype "unspecified"))
      (node (ref "CN3") (pin "92") (pinfunction "92_92") (pintype "unspecified"))
      (node (ref "CN3") (pin "95") (pinfunction "95_95") (pintype "unspecified"))
      (node (ref "CN3") (pin "98") (pinfunction "98_98") (pintype "unspecified"))
      (node (ref "D3") (pin "2") (pinfunction "2_2") (pintype "input"))
      (node (ref "FPC1") (pin "1") (pinfunction "1_1") (pintype "input"))
      (node (ref "FPC1") (pin "10") (pinfunction "10_10") (pintype "input"))
      (node (ref "FPC1") (pin "13") (pinfunction "13_13") (pintype "input"))
      (node (ref "FPC1") (pin "16") (pinfunction "16_16") (pintype "input"))
      (node (ref "FPC1") (pin "23") (pinfunction "23_23") (pintype "input"))
      (node (ref "FPC1") (pin "26") (pinfunction "26_26") (pintype "input"))
      (node (ref "FPC1") (pin "29") (pinfunction "29_29") (pintype "input"))
      (node (ref "FPC1") (pin "31") (pinfunction "31_31") (pintype "input"))
      (node (ref "FPC1") (pin "32") (pinfunction "32_32") (pintype "input"))
      (node (ref "FPC1") (pin "4") (pinfunction "4_4") (pintype "input"))
      (node (ref "FPC1") (pin "7") (pinfunction "7_7") (pintype "input"))
      (node (ref "FPC2") (pin "1") (pinfunction "1_1") (pintype "input"))
      (node (ref "FPC2") (pin "10") (pinfunction "10_10") (pintype "input"))
      (node (ref "FPC2") (pin "13") (pinfunction "13_13") (pintype "input"))
      (node (ref "FPC2") (pin "16") (pinfunction "16_16") (pintype "input"))
      (node (ref "FPC2") (pin "23") (pinfunction "23_23") (pintype "input"))
      (node (ref "FPC2") (pin "26") (pinfunction "26_26") (pintype "input"))
      (node (ref "FPC2") (pin "29") (pinfunction "29_29") (pintype "input"))
      (node (ref "FPC2") (pin "31") (pinfunction "31_31") (pintype "input"))
      (node (ref "FPC2") (pin "32") (pinfunction "32_32") (pintype "input"))
      (node (ref "FPC2") (pin "4") (pinfunction "4_4") (pintype "input"))
      (node (ref "FPC2") (pin "7") (pinfunction "7_7") (pintype "input"))
      (node (ref "H1") (pin "2") (pinfunction "2_2") (pintype "input"))
      (node (ref "H1") (pin "4") (pinfunction "4_4") (pintype "input"))
      (node (ref "H1") (pin "6") (pinfunction "6_6") (pintype "input"))
      (node (ref "H1") (pin "8") (pinfunction "8_8") (pintype "input"))
      (node (ref "HDMI1") (pin "11") (pinfunction "TMDSClockShield_11") (pintype "input"))
      (node (ref "HDMI1") (pin "17") (pinfunction "DDC/CECGround_17") (pintype "input"))
      (node (ref "HDMI1") (pin "2") (pinfunction "TMDSData2Shield_2") (pintype "input"))
      (node (ref "HDMI1") (pin "20") (pinfunction "EH_20") (pintype "input"))
      (node (ref "HDMI1") (pin "21") (pinfunction "EH_21") (pintype "input"))
      (node (ref "HDMI1") (pin "22") (pinfunction "EH_22") (pintype "input"))
      (node (ref "HDMI1") (pin "23") (pinfunction "EH_23") (pintype "input"))
      (node (ref "HDMI1") (pin "5") (pinfunction "TMDSData1Shield_5") (pintype "input"))
      (node (ref "HDMI1") (pin "8") (pinfunction "TMDSData0Shield_8") (pintype "input"))
      (node (ref "LED1") (pin "1") (pinfunction "K_1") (pintype "unspecified"))
      (node (ref "LED2") (pin "1") (pinfunction "K_1") (pintype "unspecified"))
      (node (ref "R10") (pin "2") (pinfunction "2_2") (pintype "input"))
      (node (ref "R12") (pin "1") (pinfunction "1_1") (pintype "input"))
      (node (ref "R20") (pin "1") (pinfunction "1_1") (pintype "input"))
      (node (ref "R25") (pin "1") (pinfunction "1_1") (pintype "input"))
      (node (ref "R38") (pin "1") (pinfunction "1_1") (pintype "input"))
      (node (ref "R40") (pin "1") (pinfunction "1_1") (pintype "input"))
      (node (ref "R42") (pin "1") (pinfunction "1_1") (pintype "input"))
      (node (ref "R43") (pin "1") (pinfunction "1_1") (pintype "input"))
      (node (ref "R48") (pin "1") (pinfunction "1_1") (pintype "input"))
      (node (ref "R61") (pin "1") (pinfunction "1_1") (pintype "input"))
      (node (ref "R63") (pin "1") (pinfunction "1_1") (pintype "input"))
      (node (ref "R65") (pin "1") (pinfunction "1_1") (pintype "input"))
      (node (ref "R67") (pin "2") (pinfunction "2_2") (pintype "input"))
      (node (ref "R70") (pin "2") (pinfunction "2_2") (pintype "input"))
      (node (ref "R72") (pin "2") (pinfunction "2_2") (pintype "input"))
      (node (ref "R74") (pin "2") (pinfunction "2_2") (pintype "input"))
      (node (ref "R76") (pin "2") (pinfunction "2_2") (pintype "input"))
      (node (ref "RJ1") (pin "R10") (pinfunction "GND_R10") (pintype "unspecified"))
      (node (ref "RJ2") (pin "R10") (pinfunction "GND_R10") (pintype "unspecified"))
      (node (ref "TF1") (pin "10") (pinfunction "10_10") (pintype "input"))
      (node (ref "TF1") (pin "11") (pinfunction "11_11") (pintype "input"))
      (node (ref "TF1") (pin "12") (pinfunction "12_12") (pintype "input"))
      (node (ref "TF1") (pin "13") (pinfunction "13_13") (pintype "input"))
      (node (ref "TF1") (pin "14") (pinfunction "14_14") (pintype "input"))
      (node (ref "TF1") (pin "6") (pinfunction "VSS_6") (pintype "input"))
      (node (ref "TF1") (pin "9") (pinfunction "9_9") (pintype "input"))
      (node (ref "U10") (pin "2") (pinfunction "VSS_2") (pintype "input"))
      (node (ref "U11") (pin "11") (pinfunction "PP_11") (pintype "input"))
      (node (ref "U11") (pin "2") (pinfunction "MODE/DATA_2") (pintype "bidirectional"))
      (node (ref "U11") (pin "8") (pinfunction "GND_8") (pintype "input"))
      (node (ref "U12") (pin "3") (pinfunction "GND_3") (pintype "unspecified"))
      (node (ref "U12") (pin "7") (pinfunction "DAP_7") (pintype "unspecified"))
      (node (ref "U3") (pin "1") (pinfunction "GND3_1") (pintype "unspecified"))
      (node (ref "U3") (pin "13") (pinfunction "GND1_13") (pintype "unspecified"))
      (node (ref "U3") (pin "18") (pinfunction "GND4_18") (pintype "unspecified"))
      (node (ref "U3") (pin "25") (pinfunction "EP_25") (pintype "unspecified"))
      (node (ref "U3") (pin "4") (pinfunction "AGND_4") (pintype "unspecified"))
      (node (ref "U3") (pin "6") (pinfunction "GND2_6") (pintype "unspecified"))
      (node (ref "U5") (pin "2") (pinfunction "TCK_2") (pintype "unspecified"))
      (node (ref "U5") (pin "39") (pinfunction "TEST_39") (pintype "unspecified"))
      (node (ref "U5") (pin "57") (pinfunction "EP_57") (pintype "unspecified"))
      (node (ref "U6") (pin "2") (pinfunction "VSS_2") (pintype "input"))
      (node (ref "U7") (pin "11") (pinfunction "PP_11") (pintype "input"))
      (node (ref "U7") (pin "2") (pinfunction "MODE/DATA_2") (pintype "bidirectional"))
      (node (ref "U7") (pin "8") (pinfunction "GND_8") (pintype "input"))
      (node (ref "U8") (pin "3") (pinfunction "GND_3") (pintype "unspecified"))
      (node (ref "U8") (pin "7") (pinfunction "DAP_7") (pintype "unspecified"))
      (node (ref "U9") (pin "2") (pinfunction "TCK_2") (pintype "unspecified"))
      (node (ref "U9") (pin "39") (pinfunction "TEST_39") (pintype "unspecified"))
      (node (ref "U9") (pin "57") (pinfunction "EP_57") (pintype "unspecified"))
      (node (ref "USB1") (pin "0") (pinfunction "0_0") (pintype "input"))
      (node (ref "USB1") (pin "A1") (pinfunction "GND_A1") (pintype "input"))
      (node (ref "USB1") (pin "A12") (pinfunction "GND_A12") (pintype "input"))
      (node (ref "X1") (pin "2") (pinfunction "GND_2") (pintype "unspecified"))
      (node (ref "X1") (pin "4") (pinfunction "GND_4") (pintype "unspecified"))
      (node (ref "X2") (pin "2") (pinfunction "GND_2") (pintype "unspecified"))
      (node (ref "X2") (pin "4") (pinfunction "GND_4") (pintype "unspecified"))
    )
    (net (code "93") (name "HDMI0_CEC") (class "Default")
      (node (ref "CN1") (pin "75") (pinfunction "75_75") (pintype "input"))
      (node (ref "HDMI1") (pin "13") (pinfunction "CEC_13") (pintype "input"))
    )
    (net (code "94") (name "HDMI0_CLK_N") (class "Default")
      (node (ref "CN1") (pin "45") (pinfunction "45_45") (pintype "input"))
      (node (ref "HDMI1") (pin "12") (pinfunction "TMDSClock-_12") (pintype "input"))
    )
    (net (code "95") (name "HDMI0_CLK_P") (class "Default")
      (node (ref "CN1") (pin "44") (pinfunction "44_44") (pintype "input"))
      (node (ref "HDMI1") (pin "10") (pinfunction "TMDSClock+_10") (pintype "input"))
    )
    (net (code "96") (name "HDMI0_HPD") (class "Default")
      (node (ref "CN1") (pin "74") (pinfunction "74_74") (pintype "input"))
      (node (ref "HDMI1") (pin "19") (pinfunction "HotPlugDetect_19") (pintype "input"))
    )
    (net (code "97") (name "HDMI0_SCL") (class "Default")
      (node (ref "CN1") (pin "50") (pinfunction "50_50") (pintype "input"))
      (node (ref "HDMI1") (pin "15") (pinfunction "SCL_15") (pintype "input"))
    )
    (net (code "98") (name "HDMI0_SDA") (class "Default")
      (node (ref "CN1") (pin "51") (pinfunction "51_51") (pintype "input"))
      (node (ref "HDMI1") (pin "16") (pinfunction "SDA_16") (pintype "input"))
    )
    (net (code "99") (name "HDMI0_TX0_N") (class "Default")
      (node (ref "CN1") (pin "42") (pinfunction "42_42") (pintype "input"))
      (node (ref "HDMI1") (pin "9") (pinfunction "TMDSData0-_9") (pintype "input"))
    )
    (net (code "100") (name "HDMI0_TX0_P") (class "Default")
      (node (ref "CN1") (pin "41") (pinfunction "41_41") (pintype "input"))
      (node (ref "HDMI1") (pin "7") (pinfunction "TMDSData0+_7") (pintype "input"))
    )
    (net (code "101") (name "HDMI0_TX1_N") (class "Default")
      (node (ref "CN1") (pin "39") (pinfunction "39_39") (pintype "input"))
      (node (ref "HDMI1") (pin "6") (pinfunction "TMDSData1-_6") (pintype "input"))
    )
    (net (code "102") (name "HDMI0_TX1_P") (class "Default")
      (node (ref "CN1") (pin "38") (pinfunction "38_38") (pintype "input"))
      (node (ref "HDMI1") (pin "4") (pinfunction "TMDSData1+_4") (pintype "input"))
    )
    (net (code "103") (name "HDMI0_TX2_N") (class "Default")
      (node (ref "CN1") (pin "36") (pinfunction "36_36") (pintype "input"))
      (node (ref "HDMI1") (pin "3") (pinfunction "TMDSData2-_3") (pintype "input"))
    )
    (net (code "104") (name "HDMI0_TX2_P") (class "Default")
      (node (ref "CN1") (pin "35") (pinfunction "35_35") (pintype "input"))
      (node (ref "HDMI1") (pin "1") (pinfunction "TMDSData2+_1") (pintype "input"))
    )
    (net (code "105") (name "I2C4_SCL_M3") (class "Default")
      (node (ref "CN2") (pin "15") (pinfunction "15_15") (pintype "input"))
      (node (ref "FPC1") (pin "18") (pinfunction "18_18") (pintype "input"))
    )
    (net (code "106") (name "I2C4_SDA_M3") (class "Default")
      (node (ref "CN2") (pin "14") (pinfunction "14_14") (pintype "input"))
      (node (ref "FPC1") (pin "19") (pinfunction "19_19") (pintype "input"))
    )
    (net (code "107") (name "I2C5_SCL_M2") (class "Default")
      (node (ref "CN2") (pin "20") (pinfunction "20_20") (pintype "input"))
      (node (ref "FPC2") (pin "18") (pinfunction "18_18") (pintype "input"))
    )
    (net (code "108") (name "I2C5_SDA_M2") (class "Default")
      (node (ref "CN2") (pin "22") (pinfunction "22_22") (pintype "input"))
      (node (ref "FPC2") (pin "19") (pinfunction "19_19") (pintype "input"))
    )
    (net (code "109") (name "NRPIBOOT") (class "Default")
      (node (ref "CN2") (pin "54") (pinfunction "54_54") (pintype "input"))
      (node (ref "H1") (pin "3") (pinfunction "3_3") (pintype "input"))
    )
    (net (code "110") (name "Net-(C38-Pad1)") (class "Default")
      (node (ref "C38") (pin "1") (pinfunction "1_1") (pintype "input"))
      (node (ref "RJ1") (pin "15") (pinfunction "15_15") (pintype "unspecified"))
    )
    (net (code "111") (name "Net-(C39-Pad2)") (class "Default")
      (node (ref "C39") (pin "2") (pinfunction "2_2") (pintype "input"))
      (node (ref "RJ1") (pin "16") (pinfunction "16_16") (pintype "unspecified"))
    )
    (net (code "112") (name "Net-(C70-Pad1)") (class "Default")
      (node (ref "C70") (pin "1") (pinfunction "1_1") (pintype "input"))
      (node (ref "RJ2") (pin "15") (pinfunction "15_15") (pintype "unspecified"))
    )
    (net (code "113") (name "Net-(C71-Pad2)") (class "Default")
      (node (ref "C71") (pin "2") (pinfunction "2_2") (pintype "input"))
      (node (ref "RJ2") (pin "16") (pinfunction "16_16") (pintype "unspecified"))
    )
    (net (code "114") (name "Net-(D2--)") (class "Default")
      (node (ref "D2") (pin "1") (pinfunction "-_1") (pintype "input"))
      (node (ref "F6") (pin "1") (pinfunction "1_1") (pintype "input"))
    )
    (net (code "115") (name "Net-(LED1-A)") (class "Default")
      (node (ref "LED1") (pin "2") (pinfunction "A_2") (pintype "unspecified"))
      (node (ref "R17") (pin "1") (pinfunction "1_1") (pintype "input"))
    )
    (net (code "116") (name "Net-(LED2-A)") (class "Default")
      (node (ref "LED2") (pin "2") (pinfunction "A_2") (pintype "unspecified"))
      (node (ref "R19") (pin "1") (pinfunction "1_1") (pintype "input"))
    )
    (net (code "117") (name "Net-(RJ1-CT)") (class "Default")
      (node (ref "R36") (pin "1") (pinfunction "1_1") (pintype "input"))
      (node (ref "RJ1") (pin "R1") (pinfunction "CT_R1") (pintype "unspecified"))
    )
    (net (code "118") (name "Net-(RJ1-LED1-)") (class "Default")
      (node (ref "R34") (pin "2") (pinfunction "2_2") (pintype "input"))
      (node (ref "RJ1") (pin "L2") (pinfunction "LED1-_L2") (pintype "unspecified"))
    )
    (net (code "119") (name "Net-(RJ1-LED2-)") (class "Default")
      (node (ref "R35") (pin "2") (pinfunction "2_2") (pintype "input"))
      (node (ref "RJ1") (pin "L4") (pinfunction "LED2-_L4") (pintype "unspecified"))
    )
    (net (code "120") (name "Net-(RJ2-CT)") (class "Default")
      (node (ref "R59") (pin "1") (pinfunction "1_1") (pintype "input"))
      (node (ref "RJ2") (pin "R1") (pinfunction "CT_R1") (pintype "unspecified"))
    )
    (net (code "121") (name "Net-(RJ2-LED1-)") (class "Default")
      (node (ref "R57") (pin "2") (pinfunction "2_2") (pintype "input"))
      (node (ref "RJ2") (pin "L2") (pinfunction "LED1-_L2") (pintype "unspecified"))
    )
    (net (code "122") (name "Net-(RJ2-LED2-)") (class "Default")
      (node (ref "R58") (pin "2") (pinfunction "2_2") (pintype "input"))
      (node (ref "RJ2") (pin "L4") (pinfunction "LED2-_L4") (pintype "unspecified"))
    )
    (net (code "123") (name "Net-(U3-FB1)") (class "Default")
      (node (ref "R70") (pin "1") (pinfunction "1_1") (pintype "input"))
      (node (ref "R71") (pin "2") (pinfunction "2_2") (pintype "input"))
      (node (ref "U3") (pin "14") (pinfunction "FB1_14") (pintype "unspecified"))
    )
    (net (code "124") (name "Net-(U3-FB2)") (class "Default")
      (node (ref "R72") (pin "1") (pinfunction "1_1") (pintype "input"))
      (node (ref "R73") (pin "2") (pinfunction "2_2") (pintype "input"))
      (node (ref "U3") (pin "5") (pinfunction "FB2_5") (pintype "unspecified"))
    )
    (net (code "125") (name "Net-(U3-FB3)") (class "Default")
      (node (ref "R74") (pin "1") (pinfunction "1_1") (pintype "input"))
      (node (ref "R75") (pin "2") (pinfunction "2_2") (pintype "input"))
      (node (ref "U3") (pin "2") (pinfunction "FB3_2") (pintype "unspecified"))
    )
    (net (code "126") (name "Net-(U3-FB4)") (class "Default")
      (node (ref "R76") (pin "1") (pinfunction "1_1") (pintype "input"))
      (node (ref "R77") (pin "2") (pinfunction "2_2") (pintype "input"))
      (node (ref "U3") (pin "17") (pinfunction "FB4_17") (pintype "unspecified"))
    )
    (net (code "127") (name "Net-(U3-LX1)") (class "Default")
      (node (ref "L17") (pin "2") (pinfunction "2_2") (pintype "unspecified"))
      (node (ref "U3") (pin "12") (pinfunction "LX1_12") (pintype "unspecified"))
    )
    (net (code "128") (name "Net-(U3-LX2)") (class "Default")
      (node (ref "L18") (pin "2") (pinfunction "2_2") (pintype "unspecified"))
      (node (ref "U3") (pin "7") (pinfunction "LX2_7") (pintype "unspecified"))
    )
    (net (code "129") (name "Net-(U3-LX3)") (class "Default")
      (node (ref "L1") (pin "2") (pinfunction "2_2") (pintype "unspecified"))
      (node (ref "U3") (pin "24") (pinfunction "LX3_24") (pintype "unspecified"))
    )
    (net (code "130") (name "Net-(U3-LX4)") (class "Default")
      (node (ref "L19") (pin "2") (pinfunction "2_2") (pintype "unspecified"))
      (node (ref "U3") (pin "19") (pinfunction "LX4_19") (pintype "unspecified"))
    )
    (net (code "131") (name "Net-(U5-ETHRBIAS)") (class "Default")
      (node (ref "R25") (pin "2") (pinfunction "2_2") (pintype "input"))
      (node (ref "U5") (pin "41") (pinfunction "ETHRBIAS_41") (pintype "unspecified"))
    )
    (net (code "132") (name "Net-(U5-SW_MODE)") (class "Default")
      (node (ref "R23") (pin "2") (pinfunction "2_2") (pintype "input"))
      (node (ref "U5") (pin "9") (pinfunction "SW_MODE_9") (pintype "unspecified"))
    )
    (net (code "133") (name "Net-(U5-TDI)") (class "Default")
      (node (ref "R22") (pin "2") (pinfunction "2_2") (pintype "input"))
      (node (ref "U5") (pin "1") (pinfunction "TDI_1") (pintype "unspecified"))
      (node (ref "U5") (pin "3") (pinfunction "TMS_3") (pintype "unspecified"))
    )
    (net (code "134") (name "Net-(U5-USBRBIAS)") (class "Default")
      (node (ref "R20") (pin "2") (pinfunction "2_2") (pintype "input"))
      (node (ref "U5") (pin "16") (pinfunction "USBRBIAS_16") (pintype "unspecified"))
    )
    (net (code "135") (name "Net-(U5-VBUS_DET)") (class "Default")
      (node (ref "R24") (pin "2") (pinfunction "2_2") (pintype "input"))
      (node (ref "U5") (pin "14") (pinfunction "VBUS_DET_14") (pintype "unspecified"))
    )
    (net (code "136") (name "Net-(U5-XI)") (class "Default")
      (node (ref "C67") (pin "1") (pinfunction "1_1") (pintype "input"))
      (node (ref "U5") (pin "5") (pinfunction "XI_5") (pintype "unspecified"))
      (node (ref "X1") (pin "3") (pinfunction "OSC2_3") (pintype "unspecified"))
    )
    (net (code "137") (name "Net-(U5-XO)") (class "Default")
      (node (ref "C68") (pin "2") (pinfunction "2_2") (pintype "input"))
      (node (ref "U5") (pin "6") (pinfunction "XO_6") (pintype "unspecified"))
      (node (ref "X1") (pin "1") (pinfunction "OSC1_1") (pintype "unspecified"))
    )
    (net (code "138") (name "Net-(U6-RSTIN)") (class "Default")
      (node (ref "R37") (pin "1") (pinfunction "1_1") (pintype "input"))
      (node (ref "R38") (pin "2") (pinfunction "2_2") (pintype "input"))
      (node (ref "U6") (pin "5") (pinfunction "RSTIN_5") (pintype "input"))
    )
    (net (code "139") (name "Net-(U7-ADJ2)") (class "Default")
      (node (ref "C43") (pin "2") (pinfunction "2_2") (pintype "input"))
      (node (ref "R41") (pin "1") (pinfunction "1_1") (pintype "input"))
      (node (ref "R42") (pin "2") (pinfunction "2_2") (pintype "input"))
      (node (ref "U7") (pin "1") (pinfunction "ADJ2_1") (pintype "input"))
    )
    (net (code "140") (name "Net-(U7-DEF_1)") (class "Default")
      (node (ref "R39") (pin "1") (pinfunction "1_1") (pintype "input"))
      (node (ref "R40") (pin "2") (pinfunction "2_2") (pintype "input"))
      (node (ref "U7") (pin "5") (pinfunction "DEF_1_5") (pintype "input"))
    )
    (net (code "141") (name "Net-(U7-SW1)") (class "Default")
      (node (ref "L4") (pin "1") (pinfunction "1_1") (pintype "unspecified"))
      (node (ref "U7") (pin "6") (pinfunction "SW1_6") (pintype "input"))
    )
    (net (code "142") (name "Net-(U7-SW2)") (class "Default")
      (node (ref "L5") (pin "1") (pinfunction "1_1") (pintype "unspecified"))
      (node (ref "U7") (pin "10") (pinfunction "SW2_10") (pintype "input"))
    )
    (net (code "143") (name "Net-(U9-ETHRBIAS)") (class "Default")
      (node (ref "R48") (pin "2") (pinfunction "2_2") (pintype "input"))
      (node (ref "U9") (pin "41") (pinfunction "ETHRBIAS_41") (pintype "unspecified"))
    )
    (net (code "144") (name "Net-(U9-SW_MODE)") (class "Default")
      (node (ref "R46") (pin "2") (pinfunction "2_2") (pintype "input"))
      (node (ref "U9") (pin "9") (pinfunction "SW_MODE_9") (pintype "unspecified"))
    )
    (net (code "145") (name "Net-(U9-TDI)") (class "Default")
      (node (ref "R45") (pin "2") (pinfunction "2_2") (pintype "input"))
      (node (ref "U9") (pin "1") (pinfunction "TDI_1") (pintype "unspecified"))
      (node (ref "U9") (pin "3") (pinfunction "TMS_3") (pintype "unspecified"))
    )
    (net (code "146") (name "Net-(U9-USBRBIAS)") (class "Default")
      (node (ref "R43") (pin "2") (pinfunction "2_2") (pintype "input"))
      (node (ref "U9") (pin "16") (pinfunction "USBRBIAS_16") (pintype "unspecified"))
    )
    (net (code "147") (name "Net-(U9-VBUS_DET)") (class "Default")
      (node (ref "R47") (pin "2") (pinfunction "2_2") (pintype "input"))
      (node (ref "U9") (pin "14") (pinfunction "VBUS_DET_14") (pintype "unspecified"))
    )
    (net (code "148") (name "Net-(U9-XI)") (class "Default")
      (node (ref "C100") (pin "1") (pinfunction "1_1") (pintype "input"))
      (node (ref "U9") (pin "5") (pinfunction "XI_5") (pintype "unspecified"))
      (node (ref "X2") (pin "3") (pinfunction "OSC2_3") (pintype "unspecified"))
    )
    (net (code "149") (name "Net-(U9-XO)") (class "Default")
      (node (ref "C101") (pin "2") (pinfunction "2_2") (pintype "input"))
      (node (ref "U9") (pin "6") (pinfunction "XO_6") (pintype "unspecified"))
      (node (ref "X2") (pin "1") (pinfunction "OSC1_1") (pintype "unspecified"))
    )
    (net (code "150") (name "Net-(U10-RSTIN)") (class "Default")
      (node (ref "R60") (pin "1") (pinfunction "1_1") (pintype "input"))
      (node (ref "R61") (pin "2") (pinfunction "2_2") (pintype "input"))
      (node (ref "U10") (pin "5") (pinfunction "RSTIN_5") (pintype "input"))
    )
    (net (code "151") (name "Net-(U11-ADJ2)") (class "Default")
      (node (ref "C75") (pin "2") (pinfunction "2_2") (pintype "input"))
      (node (ref "R64") (pin "1") (pinfunction "1_1") (pintype "input"))
      (node (ref "R65") (pin "2") (pinfunction "2_2") (pintype "input"))
      (node (ref "U11") (pin "1") (pinfunction "ADJ2_1") (pintype "input"))
    )
    (net (code "152") (name "Net-(U11-DEF_1)") (class "Default")
      (node (ref "R62") (pin "1") (pinfunction "1_1") (pintype "input"))
      (node (ref "R63") (pin "2") (pinfunction "2_2") (pintype "input"))
      (node (ref "U11") (pin "5") (pinfunction "DEF_1_5") (pintype "input"))
    )
    (net (code "153") (name "Net-(U11-SW1)") (class "Default")
      (node (ref "L10") (pin "1") (pinfunction "1_1") (pintype "unspecified"))
      (node (ref "U11") (pin "6") (pinfunction "SW1_6") (pintype "input"))
    )
    (net (code "154") (name "Net-(U11-SW2)") (class "Default")
      (node (ref "L11") (pin "1") (pinfunction "1_1") (pintype "unspecified"))
      (node (ref "U11") (pin "10") (pinfunction "SW2_10") (pintype "input"))
    )
    (net (code "155") (name "Net-(USB1-CC1)") (class "Default")
      (node (ref "R12") (pin "2") (pinfunction "2_2") (pintype "input"))
      (node (ref "USB1") (pin "A5") (pinfunction "CC1_A5") (pintype "input"))
    )
    (net (code "156") (name "Net-(USB1-CC2)") (class "Default")
      (node (ref "R10") (pin "1") (pinfunction "1_1") (pintype "input"))
      (node (ref "USB1") (pin "B5") (pinfunction "CC2_B5") (pintype "input"))
    )
    (net (code "157") (name "PI_LED_NACT") (class "Default")
      (node (ref "CN2") (pin "90") (pinfunction "90_90") (pintype "input"))
      (node (ref "R19") (pin "2") (pinfunction "2_2") (pintype "input"))
    )
    (net (code "158") (name "PI_LED_NPWR") (class "Default")
      (node (ref "CN2") (pin "53") (pinfunction "53_53") (pintype "input"))
      (node (ref "R17") (pin "2") (pinfunction "2_2") (pintype "input"))
    )
    (net (code "159") (name "SD_CLK") (class "Default")
      (node (ref "CN2") (pin "72") (pinfunction "72_72") (pintype "input"))
      (node (ref "TF1") (pin "5") (pinfunction "CLK_5") (pintype "input"))
    )
    (net (code "160") (name "SD_CMD") (class "Default")
      (node (ref "CN2") (pin "31") (pinfunction "31_31") (pintype "input"))
      (node (ref "TF1") (pin "3") (pinfunction "CMD_3") (pintype "input"))
    )
    (net (code "161") (name "SD_DAT0") (class "Default")
      (node (ref "CN2") (pin "69") (pinfunction "69_69") (pintype "input"))
      (node (ref "TF1") (pin "7") (pinfunction "DAT0_7") (pintype "input"))
    )
    (net (code "162") (name "SD_DAT1") (class "Default")
      (node (ref "CN2") (pin "67") (pinfunction "67_67") (pintype "input"))
      (node (ref "TF1") (pin "8") (pinfunction "DAT1_8") (pintype "input"))
    )
    (net (code "163") (name "SD_DAT2") (class "Default")
      (node (ref "CN2") (pin "66") (pinfunction "66_66") (pintype "input"))
      (node (ref "TF1") (pin "1") (pinfunction "DAT2_1") (pintype "input"))
    )
    (net (code "164") (name "SD_DAT3") (class "Default")
      (node (ref "CN2") (pin "70") (pinfunction "70_70") (pintype "input"))
      (node (ref "TF1") (pin "2") (pinfunction "CD/DAT3_2") (pintype "input"))
    )
    (net (code "165") (name "USB_N") (class "Default")
      (node (ref "CN1") (pin "99") (pinfunction "99_99") (pintype "input"))
      (node (ref "D3") (pin "3") (pinfunction "3_3") (pintype "input"))
      (node (ref "D3") (pin "4") (pinfunction "4_4") (pintype "input"))
      (node (ref "USB1") (pin "A7") (pinfunction "DN1_A7") (pintype "input"))
      (node (ref "USB1") (pin "B7") (pinfunction "DN2_B7") (pintype "input"))
    )
    (net (code "166") (name "USB_OTG_ID") (class "Default")
      (node (ref "CN1") (pin "100") (pinfunction "100_100") (pintype "input"))
      (node (ref "H1") (pin "7") (pinfunction "7_7") (pintype "input"))
    )
    (net (code "167") (name "USB_P") (class "Default")
      (node (ref "CN1") (pin "98") (pinfunction "98_98") (pintype "input"))
      (node (ref "D3") (pin "1") (pinfunction "1_1") (pintype "input"))
      (node (ref "D3") (pin "6") (pinfunction "6_6") (pintype "input"))
      (node (ref "USB1") (pin "A6") (pinfunction "DP1_A6") (pintype "input"))
      (node (ref "USB1") (pin "B6") (pinfunction "DP2_B6") (pintype "input"))
    )
    (net (code "168") (name "unconnected-(CN1-Pad1)") (class "Default")
      (node (ref "CN1") (pin "1") (pinfunction "1_1") (pintype "input+no_connect"))
    )
    (net (code "169") (name "unconnected-(CN1-Pad2)") (class "Default")
      (node (ref "CN1") (pin "2") (pinfunction "2_2") (pintype "input+no_connect"))
    )
    (net (code "170") (name "unconnected-(CN1-Pad3)") (class "Default")
      (node (ref "CN1") (pin "3") (pinfunction "3_3") (pintype "input+no_connect"))
    )
    (net (code "171") (name "unconnected-(CN1-Pad5)") (class "Default")
      (node (ref "CN1") (pin "5") (pinfunction "5_5") (pintype "input+no_connect"))
    )
    (net (code "172") (name "unconnected-(CN1-Pad6)") (class "Default")
      (node (ref "CN1") (pin "6") (pinfunction "6_6") (pintype "input+no_connect"))
    )
    (net (code "173") (name "unconnected-(CN1-Pad8)") (class "Default")
      (node (ref "CN1") (pin "8") (pinfunction "8_8") (pintype "input+no_connect"))
    )
    (net (code "174") (name "unconnected-(CN1-Pad9)") (class "Default")
      (node (ref "CN1") (pin "9") (pinfunction "9_9") (pintype "input+no_connect"))
    )
    (net (code "175") (name "unconnected-(CN1-Pad11)") (class "Default")
      (node (ref "CN1") (pin "11") (pinfunction "11_11") (pintype "input+no_connect"))
    )
    (net (code "176") (name "unconnected-(CN1-Pad12)") (class "Default")
      (node (ref "CN1") (pin "12") (pinfunction "12_12") (pintype "input+no_connect"))
    )
    (net (code "177") (name "unconnected-(CN1-Pad23)") (class "Default")
      (node (ref "CN1") (pin "23") (pinfunction "23_23") (pintype "input+no_connect"))
    )
    (net (code "178") (name "unconnected-(CN1-Pad24)") (class "Default")
      (node (ref "CN1") (pin "24") (pinfunction "24_24") (pintype "input+no_connect"))
    )
    (net (code "179") (name "unconnected-(CN1-Pad26)") (class "Default")
      (node (ref "CN1") (pin "26") (pinfunction "26_26") (pintype "input+no_connect"))
    )
    (net (code "180") (name "unconnected-(CN1-Pad27)") (class "Default")
      (node (ref "CN1") (pin "27") (pinfunction "27_27") (pintype "input+no_connect"))
    )
    (net (code "181") (name "unconnected-(CN1-Pad29)") (class "Default")
      (node (ref "CN1") (pin "29") (pinfunction "29_29") (pintype "input+no_connect"))
    )
    (net (code "182") (name "unconnected-(CN1-Pad30)") (class "Default")
      (node (ref "CN1") (pin "30") (pinfunction "30_30") (pintype "input+no_connect"))
    )
    (net (code "183") (name "unconnected-(CN1-Pad32)") (class "Default")
      (node (ref "CN1") (pin "32") (pinfunction "32_32") (pintype "input+no_connect"))
    )
    (net (code "184") (name "unconnected-(CN1-Pad33)") (class "Default")
      (node (ref "CN1") (pin "33") (pinfunction "33_33") (pintype "input+no_connect"))
    )
    (net (code "185") (name "unconnected-(CN1-Pad47)") (class "Default")
      (node (ref "CN1") (pin "47") (pinfunction "47_47") (pintype "input+no_connect"))
    )
    (net (code "186") (name "unconnected-(CN1-Pad48)") (class "Default")
      (node (ref "CN1") (pin "48") (pinfunction "48_48") (pintype "input+no_connect"))
    )
    (net (code "187") (name "unconnected-(CN1-Pad53)") (class "Default")
      (node (ref "CN1") (pin "53") (pinfunction "53_53") (pintype "input+no_connect"))
    )
    (net (code "188") (name "unconnected-(CN1-Pad54)") (class "Default")
      (node (ref "CN1") (pin "54") (pinfunction "54_54") (pintype "input+no_connect"))
    )
    (net (code "189") (name "unconnected-(CN1-Pad56)") (class "Default")
      (node (ref "CN1") (pin "56") (pinfunction "56_56") (pintype "input+no_connect"))
    )
    (net (code "190") (name "unconnected-(CN1-Pad57)") (class "Default")
      (node (ref "CN1") (pin "57") (pinfunction "57_57") (pintype "input+no_connect"))
    )
    (net (code "191") (name "unconnected-(CN1-Pad59)") (class "Default")
      (node (ref "CN1") (pin "59") (pinfunction "59_59") (pintype "input+no_connect"))
    )
    (net (code "192") (name "unconnected-(CN1-Pad60)") (class "Default")
      (node (ref "CN1") (pin "60") (pinfunction "60_60") (pintype "input+no_connect"))
    )
    (net (code "193") (name "unconnected-(CN1-Pad62)") (class "Default")
      (node (ref "CN1") (pin "62") (pinfunction "62_62") (pintype "input+no_connect"))
    )
    (net (code "194") (name "unconnected-(CN1-Pad63)") (class "Default")
      (node (ref "CN1") (pin "63") (pinfunction "63_63") (pintype "input+no_connect"))
    )
    (net (code "195") (name "unconnected-(CN1-Pad65)") (class "Default")
      (node (ref "CN1") (pin "65") (pinfunction "65_65") (pintype "input+no_connect"))
    )
    (net (code "196") (name "unconnected-(CN1-Pad66)") (class "Default")
      (node (ref "CN1") (pin "66") (pinfunction "66_66") (pintype "input+no_connect"))
    )
    (net (code "197") (name "unconnected-(CN1-Pad68)") (class "Default")
      (node (ref "CN1") (pin "68") (pinfunction "68_68") (pintype "input+no_connect"))
    )
    (net (code "198") (name "unconnected-(CN1-Pad69)") (class "Default")
      (node (ref "CN1") (pin "69") (pinfunction "69_69") (pintype "input+no_connect"))
    )
    (net (code "199") (name "unconnected-(CN1-Pad71)") (class "Default")
      (node (ref "CN1") (pin "71") (pinfunction "71_71") (pintype "input+no_connect"))
    )
    (net (code "200") (name "unconnected-(CN1-Pad72)") (class "Default")
      (node (ref "CN1") (pin "72") (pinfunction "72_72") (pintype "input+no_connect"))
    )
    (net (code "201") (name "unconnected-(CN1-Pad76)") (class "Default")
      (node (ref "CN1") (pin "76") (pinfunction "76_76") (pintype "input+no_connect"))
    )
    (net (code "202") (name "unconnected-(CN1-Pad77)") (class "Default")
      (node (ref "CN1") (pin "77") (pinfunction "77_77") (pintype "input+no_connect"))
    )
    (net (code "203") (name "unconnected-(CN1-Pad78)") (class "Default")
      (node (ref "CN1") (pin "78") (pinfunction "78_78") (pintype "input+no_connect"))
    )
    (net (code "204") (name "unconnected-(CN1-Pad79)") (class "Default")
      (node (ref "CN1") (pin "79") (pinfunction "79_79") (pintype "input+no_connect"))
    )
    (net (code "205") (name "unconnected-(CN1-Pad95)") (class "Default")
      (node (ref "CN1") (pin "95") (pinfunction "95_95") (pintype "input+no_connect"))
    )
    (net (code "206") (name "unconnected-(CN1-Pad96)") (class "Default")
      (node (ref "CN1") (pin "96") (pinfunction "96_96") (pintype "input+no_connect"))
    )
    (net (code "207") (name "unconnected-(CN2-Pad2)") (class "Default")
      (node (ref "CN2") (pin "2") (pinfunction "2_2") (pintype "input+no_connect"))
    )
    (net (code "208") (name "unconnected-(CN2-Pad3)") (class "Default")
      (node (ref "CN2") (pin "3") (pinfunction "3_3") (pintype "input+no_connect"))
    )
    (net (code "209") (name "unconnected-(CN2-Pad5)") (class "Default")
      (node (ref "CN2") (pin "5") (pinfunction "5_5") (pintype "input+no_connect"))
    )
    (net (code "210") (name "unconnected-(CN2-Pad6)") (class "Default")
      (node (ref "CN2") (pin "6") (pinfunction "6_6") (pintype "input+no_connect"))
    )
    (net (code "211") (name "unconnected-(CN2-Pad8)") (class "Default")
      (node (ref "CN2") (pin "8") (pinfunction "8_8") (pintype "input+no_connect"))
    )
    (net (code "212") (name "unconnected-(CN2-Pad9)") (class "Default")
      (node (ref "CN2") (pin "9") (pinfunction "9_9") (pintype "input+no_connect"))
    )
    (net (code "213") (name "unconnected-(CN2-Pad10)") (class "Default")
      (node (ref "CN2") (pin "10") (pinfunction "10_10") (pintype "input+no_connect"))
    )
    (net (code "214") (name "unconnected-(CN2-Pad12)") (class "Default")
      (node (ref "CN2") (pin "12") (pinfunction "12_12") (pintype "input+no_connect"))
    )
    (net (code "215") (name "unconnected-(CN2-Pad13)") (class "Default")
      (node (ref "CN2") (pin "13") (pinfunction "13_13") (pintype "input+no_connect"))
    )
    (net (code "216") (name "unconnected-(CN2-Pad17)") (class "Default")
      (node (ref "CN2") (pin "17") (pinfunction "17_17") (pintype "input+no_connect"))
    )
    (net (code "217") (name "unconnected-(CN2-Pad18)") (class "Default")
      (node (ref "CN2") (pin "18") (pinfunction "18_18") (pintype "input+no_connect"))
    )
    (net (code "218") (name "unconnected-(CN2-Pad19)") (class "Default")
      (node (ref "CN2") (pin "19") (pinfunction "19_19") (pintype "input+no_connect"))
    )
    (net (code "219") (name "unconnected-(CN2-Pad23)") (class "Default")
      (node (ref "CN2") (pin "23") (pinfunction "23_23") (pintype "input+no_connect"))
    )
    (net (code "220") (name "unconnected-(CN2-Pad24)") (class "Default")
      (node (ref "CN2") (pin "24") (pinfunction "24_24") (pintype "input+no_connect"))
    )
    (net (code "221") (name "unconnected-(CN2-Pad25)") (class "Default")
      (node (ref "CN2") (pin "25") (pinfunction "25_25") (pintype "input+no_connect"))
    )
    (net (code "222") (name "unconnected-(CN2-Pad27)") (class "Default")
      (node (ref "CN2") (pin "27") (pinfunction "27_27") (pintype "input+no_connect"))
    )
    (net (code "223") (name "unconnected-(CN2-Pad28)") (class "Default")
      (node (ref "CN2") (pin "28") (pinfunction "28_28") (pintype "input+no_connect"))
    )
    (net (code "224") (name "unconnected-(CN2-Pad32)") (class "Default")
      (node (ref "CN2") (pin "32") (pinfunction "32_32") (pintype "input+no_connect"))
    )
    (net (code "225") (name "unconnected-(CN2-Pad34)") (class "Default")
      (node (ref "CN2") (pin "34") (pinfunction "34_34") (pintype "input+no_connect"))
    )
    (net (code "226") (name "unconnected-(CN2-Pad35)") (class "Default")
      (node (ref "CN2") (pin "35") (pinfunction "35_35") (pintype "input+no_connect"))
    )
    (net (code "227") (name "unconnected-(CN2-Pad36)") (class "Default")
      (node (ref "CN2") (pin "36") (pinfunction "36_36") (pintype "input+no_connect"))
    )
    (net (code "228") (name "unconnected-(CN2-Pad38)") (class "Default")
      (node (ref "CN2") (pin "38") (pinfunction "38_38") (pintype "input+no_connect"))
    )
    (net (code "229") (name "unconnected-(CN2-Pad40)") (class "Default")
      (node (ref "CN2") (pin "40") (pinfunction "40_40") (pintype "input+no_connect"))
    )
    (net (code "230") (name "unconnected-(CN2-Pad41)") (class "Default")
      (node (ref "CN2") (pin "41") (pinfunction "41_41") (pintype "input+no_connect"))
    )
    (net (code "231") (name "unconnected-(CN2-Pad46)") (class "Default")
      (node (ref "CN2") (pin "46") (pinfunction "46_46") (pintype "input+no_connect"))
    )
    (net (code "232") (name "unconnected-(CN2-Pad47)") (class "Default")
      (node (ref "CN2") (pin "47") (pinfunction "47_47") (pintype "input+no_connect"))
    )
    (net (code "233") (name "unconnected-(CN2-Pad48)") (class "Default")
      (node (ref "CN2") (pin "48") (pinfunction "48_48") (pintype "input+no_connect"))
    )
    (net (code "234") (name "unconnected-(CN2-Pad50)") (class "Default")
      (node (ref "CN2") (pin "50") (pinfunction "50_50") (pintype "input+no_connect"))
    )
    (net (code "235") (name "unconnected-(CN2-Pad52)") (class "Default")
      (node (ref "CN2") (pin "52") (pinfunction "52_52") (pintype "input+no_connect"))
    )
    (net (code "236") (name "unconnected-(CN2-Pad55)") (class "Default")
      (node (ref "CN2") (pin "55") (pinfunction "55_55") (pintype "input+no_connect"))
    )
    (net (code "237") (name "unconnected-(CN2-Pad56)") (class "Default")
      (node (ref "CN2") (pin "56") (pinfunction "56_56") (pintype "input+no_connect"))
    )
    (net (code "238") (name "unconnected-(CN2-Pad63)") (class "Default")
      (node (ref "CN2") (pin "63") (pinfunction "63_63") (pintype "input+no_connect"))
    )
    (net (code "239") (name "unconnected-(CN2-Pad64)") (class "Default")
      (node (ref "CN2") (pin "64") (pinfunction "64_64") (pintype "input+no_connect"))
    )
    (net (code "240") (name "unconnected-(CN2-Pad73)") (class "Default")
      (node (ref "CN2") (pin "73") (pinfunction "73_73") (pintype "input+no_connect"))
    )
    (net (code "241") (name "unconnected-(CN2-Pad75)") (class "Default")
      (node (ref "CN2") (pin "75") (pinfunction "75_75") (pintype "input+no_connect"))
    )
    (net (code "242") (name "unconnected-(CN2-Pad76)") (class "Default")
      (node (ref "CN2") (pin "76") (pinfunction "76_76") (pintype "input+no_connect"))
    )
    (net (code "243") (name "unconnected-(CN2-Pad77)") (class "Default")
      (node (ref "CN2") (pin "77") (pinfunction "77_77") (pintype "input+no_connect"))
    )
    (net (code "244") (name "unconnected-(CN2-Pad78)") (class "Default")
      (node (ref "CN2") (pin "78") (pinfunction "78_78") (pintype "input+no_connect"))
    )
    (net (code "245") (name "unconnected-(CN2-Pad81)") (class "Default")
      (node (ref "CN2") (pin "81") (pinfunction "81_81") (pintype "input+no_connect"))
    )
    (net (code "246") (name "unconnected-(CN2-Pad82)") (class "Default")
      (node (ref "CN2") (pin "82") (pinfunction "82_82") (pintype "input+no_connect"))
    )
    (net (code "247") (name "unconnected-(CN2-Pad83)") (class "Default")
      (node (ref "CN2") (pin "83") (pinfunction "83_83") (pintype "input+no_connect"))
    )
    (net (code "248") (name "unconnected-(CN2-Pad85)") (class "Default")
      (node (ref "CN2") (pin "85") (pinfunction "85_85") (pintype "input+no_connect"))
    )
    (net (code "249") (name "unconnected-(CN2-Pad86)") (class "Default")
      (node (ref "CN2") (pin "86") (pinfunction "86_86") (pintype "input+no_connect"))
    )
    (net (code "250") (name "unconnected-(CN2-Pad87)") (class "Default")
      (node (ref "CN2") (pin "87") (pinfunction "87_87") (pintype "input+no_connect"))
    )
    (net (code "251") (name "unconnected-(CN2-Pad88)") (class "Default")
      (node (ref "CN2") (pin "88") (pinfunction "88_88") (pintype "input+no_connect"))
    )
    (net (code "252") (name "unconnected-(CN2-Pad91)") (class "Default")
      (node (ref "CN2") (pin "91") (pinfunction "91_91") (pintype "input+no_connect"))
    )
    (net (code "253") (name "unconnected-(CN2-Pad92)") (class "Default")
      (node (ref "CN2") (pin "92") (pinfunction "92_92") (pintype "input+no_connect"))
    )
    (net (code "254") (name "unconnected-(CN2-Pad93)") (class "Default")
      (node (ref "CN2") (pin "93") (pinfunction "93_93") (pintype "input+no_connect"))
    )
    (net (code "255") (name "unconnected-(CN2-Pad95)") (class "Default")
      (node (ref "CN2") (pin "95") (pinfunction "95_95") (pintype "input+no_connect"))
    )
    (net (code "256") (name "unconnected-(CN2-Pad96)") (class "Default")
      (node (ref "CN2") (pin "96") (pinfunction "96_96") (pintype "input+no_connect"))
    )
    (net (code "257") (name "unconnected-(CN2-Pad98)") (class "Default")
      (node (ref "CN2") (pin "98") (pinfunction "98_98") (pintype "input+no_connect"))
    )
    (net (code "258") (name "unconnected-(CN2-Pad99)") (class "Default")
      (node (ref "CN2") (pin "99") (pinfunction "99_99") (pintype "input+no_connect"))
    )
    (net (code "259") (name "unconnected-(CN3-Pad1)") (class "Default")
      (node (ref "CN3") (pin "1") (pinfunction "1_1") (pintype "unspecified+no_connect"))
    )
    (net (code "260") (name "unconnected-(CN3-Pad2)") (class "Default")
      (node (ref "CN3") (pin "2") (pinfunction "2_2") (pintype "unspecified+no_connect"))
    )
    (net (code "261") (name "unconnected-(CN3-Pad4)") (class "Default")
      (node (ref "CN3") (pin "4") (pinfunction "4_4") (pintype "unspecified+no_connect"))
    )
    (net (code "262") (name "unconnected-(CN3-Pad5)") (class "Default")
      (node (ref "CN3") (pin "5") (pinfunction "5_5") (pintype "unspecified+no_connect"))
    )
    (net (code "263") (name "unconnected-(CN3-Pad7)") (class "Default")
      (node (ref "CN3") (pin "7") (pinfunction "7_7") (pintype "unspecified+no_connect"))
    )
    (net (code "264") (name "unconnected-(CN3-Pad8)") (class "Default")
      (node (ref "CN3") (pin "8") (pinfunction "8_8") (pintype "unspecified+no_connect"))
    )
    (net (code "265") (name "unconnected-(CN3-Pad10)") (class "Default")
      (node (ref "CN3") (pin "10") (pinfunction "10_10") (pintype "unspecified+no_connect"))
    )
    (net (code "266") (name "unconnected-(CN3-Pad11)") (class "Default")
      (node (ref "CN3") (pin "11") (pinfunction "11_11") (pintype "unspecified+no_connect"))
    )
    (net (code "267") (name "unconnected-(CN3-Pad12)") (class "Default")
      (node (ref "CN3") (pin "12") (pinfunction "12_12") (pintype "unspecified+no_connect"))
    )
    (net (code "268") (name "unconnected-(CN3-Pad13)") (class "Default")
      (node (ref "CN3") (pin "13") (pinfunction "13_13") (pintype "unspecified+no_connect"))
    )
    (net (code "269") (name "unconnected-(CN3-Pad14)") (class "Default")
      (node (ref "CN3") (pin "14") (pinfunction "14_14") (pintype "unspecified+no_connect"))
    )
    (net (code "270") (name "unconnected-(CN3-Pad15)") (class "Default")
      (node (ref "CN3") (pin "15") (pinfunction "15_15") (pintype "unspecified+no_connect"))
    )
    (net (code "271") (name "unconnected-(CN3-Pad17)") (class "Default")
      (node (ref "CN3") (pin "17") (pinfunction "17_17") (pintype "unspecified+no_connect"))
    )
    (net (code "272") (name "unconnected-(CN3-Pad18)") (class "Default")
      (node (ref "CN3") (pin "18") (pinfunction "18_18") (pintype "unspecified+no_connect"))
    )
    (net (code "273") (name "unconnected-(CN3-Pad19)") (class "Default")
      (node (ref "CN3") (pin "19") (pinfunction "19_19") (pintype "unspecified+no_connect"))
    )
    (net (code "274") (name "unconnected-(CN3-Pad20)") (class "Default")
      (node (ref "CN3") (pin "20") (pinfunction "20_20") (pintype "unspecified+no_connect"))
    )
    (net (code "275") (name "unconnected-(CN3-Pad21)") (class "Default")
      (node (ref "CN3") (pin "21") (pinfunction "21_21") (pintype "unspecified+no_connect"))
    )
    (net (code "276") (name "unconnected-(CN3-Pad23)") (class "Default")
      (node (ref "CN3") (pin "23") (pinfunction "23_23") (pintype "unspecified+no_connect"))
    )
    (net (code "277") (name "unconnected-(CN3-Pad24)") (class "Default")
      (node (ref "CN3") (pin "24") (pinfunction "24_24") (pintype "unspecified+no_connect"))
    )
    (net (code "278") (name "unconnected-(CN3-Pad25)") (class "Default")
      (node (ref "CN3") (pin "25") (pinfunction "25_25") (pintype "unspecified+no_connect"))
    )
    (net (code "279") (name "unconnected-(CN3-Pad26)") (class "Default")
      (node (ref "CN3") (pin "26") (pinfunction "26_26") (pintype "unspecified+no_connect"))
    )
    (net (code "280") (name "unconnected-(CN3-Pad28)") (class "Default")
      (node (ref "CN3") (pin "28") (pinfunction "28_28") (pintype "unspecified+no_connect"))
    )
    (net (code "281") (name "unconnected-(CN3-Pad29)") (class "Default")
      (node (ref "CN3") (pin "29") (pinfunction "29_29") (pintype "unspecified+no_connect"))
    )
    (net (code "282") (name "unconnected-(CN3-Pad30)") (class "Default")
      (node (ref "CN3") (pin "30") (pinfunction "30_30") (pintype "unspecified+no_connect"))
    )
    (net (code "283") (name "unconnected-(CN3-Pad31)") (class "Default")
      (node (ref "CN3") (pin "31") (pinfunction "31_31") (pintype "unspecified+no_connect"))
    )
    (net (code "284") (name "unconnected-(CN3-Pad33)") (class "Default")
      (node (ref "CN3") (pin "33") (pinfunction "33_33") (pintype "unspecified+no_connect"))
    )
    (net (code "285") (name "unconnected-(CN3-Pad34)") (class "Default")
      (node (ref "CN3") (pin "34") (pinfunction "34_34") (pintype "unspecified+no_connect"))
    )
    (net (code "286") (name "unconnected-(CN3-Pad35)") (class "Default")
      (node (ref "CN3") (pin "35") (pinfunction "35_35") (pintype "unspecified+no_connect"))
    )
    (net (code "287") (name "unconnected-(CN3-Pad36)") (class "Default")
      (node (ref "CN3") (pin "36") (pinfunction "36_36") (pintype "unspecified+no_connect"))
    )
    (net (code "288") (name "unconnected-(CN3-Pad38)") (class "Default")
      (node (ref "CN3") (pin "38") (pinfunction "38_38") (pintype "unspecified+no_connect"))
    )
    (net (code "289") (name "unconnected-(CN3-Pad39)") (class "Default")
      (node (ref "CN3") (pin "39") (pinfunction "39_39") (pintype "unspecified+no_connect"))
    )
    (net (code "290") (name "unconnected-(CN3-Pad41)") (class "Default")
      (node (ref "CN3") (pin "41") (pinfunction "41_41") (pintype "unspecified+no_connect"))
    )
    (net (code "291") (name "unconnected-(CN3-Pad42)") (class "Default")
      (node (ref "CN3") (pin "42") (pinfunction "42_42") (pintype "unspecified+no_connect"))
    )
    (net (code "292") (name "unconnected-(CN3-Pad44)") (class "Default")
      (node (ref "CN3") (pin "44") (pinfunction "44_44") (pintype "unspecified+no_connect"))
    )
    (net (code "293") (name "unconnected-(CN3-Pad45)") (class "Default")
      (node (ref "CN3") (pin "45") (pinfunction "45_45") (pintype "unspecified+no_connect"))
    )
    (net (code "294") (name "unconnected-(CN3-Pad47)") (class "Default")
      (node (ref "CN3") (pin "47") (pinfunction "47_47") (pintype "unspecified+no_connect"))
    )
    (net (code "295") (name "unconnected-(CN3-Pad48)") (class "Default")
      (node (ref "CN3") (pin "48") (pinfunction "48_48") (pintype "unspecified+no_connect"))
    )
    (net (code "296") (name "unconnected-(CN3-Pad49)") (class "Default")
      (node (ref "CN3") (pin "49") (pinfunction "49_49") (pintype "unspecified+no_connect"))
    )
    (net (code "297") (name "unconnected-(CN3-Pad52)") (class "Default")
      (node (ref "CN3") (pin "52") (pinfunction "52_52") (pintype "unspecified+no_connect"))
    )
    (net (code "298") (name "unconnected-(CN3-Pad53)") (class "Default")
      (node (ref "CN3") (pin "53") (pinfunction "53_53") (pintype "unspecified+no_connect"))
    )
    (net (code "299") (name "unconnected-(CN3-Pad54)") (class "Default")
      (node (ref "CN3") (pin "54") (pinfunction "54_54") (pintype "unspecified+no_connect"))
    )
    (net (code "300") (name "unconnected-(CN3-Pad55)") (class "Default")
      (node (ref "CN3") (pin "55") (pinfunction "55_55") (pintype "unspecified+no_connect"))
    )
    (net (code "301") (name "unconnected-(CN3-Pad56)") (class "Default")
      (node (ref "CN3") (pin "56") (pinfunction "56_56") (pintype "unspecified+no_connect"))
    )
    (net (code "302") (name "unconnected-(CN3-Pad58)") (class "Default")
      (node (ref "CN3") (pin "58") (pinfunction "58_58") (pintype "unspecified+no_connect"))
    )
    (net (code "303") (name "unconnected-(CN3-Pad59)") (class "Default")
      (node (ref "CN3") (pin "59") (pinfunction "59_59") (pintype "unspecified+no_connect"))
    )
    (net (code "304") (name "unconnected-(CN3-Pad60)") (class "Default")
      (node (ref "CN3") (pin "60") (pinfunction "60_60") (pintype "unspecified+no_connect"))
    )
    (net (code "305") (name "unconnected-(CN3-Pad61)") (class "Default")
      (node (ref "CN3") (pin "61") (pinfunction "61_61") (pintype "unspecified+no_connect"))
    )
    (net (code "306") (name "unconnected-(CN3-Pad62)") (class "Default")
      (node (ref "CN3") (pin "62") (pinfunction "62_62") (pintype "unspecified+no_connect"))
    )
    (net (code "307") (name "unconnected-(CN3-Pad64)") (class "Default")
      (node (ref "CN3") (pin "64") (pinfunction "64_64") (pintype "unspecified+no_connect"))
    )
    (net (code "308") (name "unconnected-(CN3-Pad65)") (class "Default")
      (node (ref "CN3") (pin "65") (pinfunction "65_65") (pintype "unspecified+no_connect"))
    )
    (net (code "309") (name "unconnected-(CN3-Pad66)") (class "Default")
      (node (ref "CN3") (pin "66") (pinfunction "66_66") (pintype "unspecified+no_connect"))
    )
    (net (code "310") (name "unconnected-(CN3-Pad67)") (class "Default")
      (node (ref "CN3") (pin "67") (pinfunction "67_67") (pintype "unspecified+no_connect"))
    )
    (net (code "311") (name "unconnected-(CN3-Pad69)") (class "Default")
      (node (ref "CN3") (pin "69") (pinfunction "69_69") (pintype "unspecified+no_connect"))
    )
    (net (code "312") (name "unconnected-(CN3-Pad70)") (class "Default")
      (node (ref "CN3") (pin "70") (pinfunction "70_70") (pintype "unspecified+no_connect"))
    )
    (net (code "313") (name "unconnected-(CN3-Pad71)") (class "Default")
      (node (ref "CN3") (pin "71") (pinfunction "71_71") (pintype "unspecified+no_connect"))
    )
    (net (code "314") (name "unconnected-(CN3-Pad72)") (class "Default")
      (node (ref "CN3") (pin "72") (pinfunction "72_72") (pintype "unspecified+no_connect"))
    )
    (net (code "315") (name "unconnected-(CN3-Pad74)") (class "Default")
      (node (ref "CN3") (pin "74") (pinfunction "74_74") (pintype "unspecified+no_connect"))
    )
    (net (code "316") (name "unconnected-(CN3-Pad75)") (class "Default")
      (node (ref "CN3") (pin "75") (pinfunction "75_75") (pintype "unspecified+no_connect"))
    )
    (net (code "317") (name "unconnected-(CN3-Pad76)") (class "Default")
      (node (ref "CN3") (pin "76") (pinfunction "76_76") (pintype "unspecified+no_connect"))
    )
    (net (code "318") (name "unconnected-(CN3-Pad77)") (class "Default")
      (node (ref "CN3") (pin "77") (pinfunction "77_77") (pintype "unspecified+no_connect"))
    )
    (net (code "319") (name "unconnected-(CN3-Pad79)") (class "Default")
      (node (ref "CN3") (pin "79") (pinfunction "79_79") (pintype "unspecified+no_connect"))
    )
    (net (code "320") (name "unconnected-(CN3-Pad87)") (class "Default")
      (node (ref "CN3") (pin "87") (pinfunction "87_87") (pintype "unspecified+no_connect"))
    )
    (net (code "321") (name "unconnected-(CN3-Pad88)") (class "Default")
      (node (ref "CN3") (pin "88") (pinfunction "88_88") (pintype "unspecified+no_connect"))
    )
    (net (code "322") (name "unconnected-(CN3-Pad90)") (class "Default")
      (node (ref "CN3") (pin "90") (pinfunction "90_90") (pintype "unspecified+no_connect"))
    )
    (net (code "323") (name "unconnected-(CN3-Pad91)") (class "Default")
      (node (ref "CN3") (pin "91") (pinfunction "91_91") (pintype "unspecified+no_connect"))
    )
    (net (code "324") (name "unconnected-(CN3-Pad96)") (class "Default")
      (node (ref "CN3") (pin "96") (pinfunction "96_96") (pintype "unspecified+no_connect"))
    )
    (net (code "325") (name "unconnected-(CN3-Pad97)") (class "Default")
      (node (ref "CN3") (pin "97") (pinfunction "97_97") (pintype "unspecified+no_connect"))
    )
    (net (code "326") (name "unconnected-(FPC1-Pad20)") (class "Default")
      (node (ref "FPC1") (pin "20") (pinfunction "20_20") (pintype "input+no_connect"))
    )
    (net (code "327") (name "unconnected-(FPC1-Pad21)") (class "Default")
      (node (ref "FPC1") (pin "21") (pinfunction "21_21") (pintype "input+no_connect"))
    )
    (net (code "328") (name "unconnected-(FPC2-Pad20)") (class "Default")
      (node (ref "FPC2") (pin "20") (pinfunction "20_20") (pintype "input+no_connect"))
    )
    (net (code "329") (name "unconnected-(FPC2-Pad21)") (class "Default")
      (node (ref "FPC2") (pin "21") (pinfunction "21_21") (pintype "input+no_connect"))
    )
    (net (code "330") (name "unconnected-(HDMI1-Reserved(N.C.)-Pad14)") (class "Default")
      (node (ref "HDMI1") (pin "14") (pinfunction "Reserved(N.C.)_14") (pintype "input+no_connect"))
    )
    (net (code "331") (name "unconnected-(U3-NC-Pad15)") (class "Default")
      (node (ref "U3") (pin "15") (pinfunction "NC_15") (pintype "unspecified+no_connect"))
    )
    (net (code "332") (name "unconnected-(U3-NC-Pad16)") (class "Default")
      (node (ref "U3") (pin "16") (pinfunction "NC_16") (pintype "unspecified+no_connect"))
    )
    (net (code "333") (name "unconnected-(U5-GPIO2{slash}LED2-Pad33)") (class "Default")
      (node (ref "U5") (pin "33") (pinfunction "GPIO2/LED2_33") (pintype "unspecified+no_connect"))
    )
    (net (code "334") (name "unconnected-(U5-GPIO3{slash}LED3-Pad34)") (class "Default")
      (node (ref "U5") (pin "34") (pinfunction "GPIO3/LED3_34") (pintype "unspecified+no_connect"))
    )
    (net (code "335") (name "unconnected-(U5-GPIO5{slash}PME-Pad38)") (class "Default")
      (node (ref "U5") (pin "38") (pinfunction "GPIO5/PME_38") (pintype "unspecified+no_connect"))
    )
    (net (code "336") (name "unconnected-(U5-GPIO6{slash}PME_MODE_SEL-Pad40)") (class "Default")
      (node (ref "U5") (pin "40") (pinfunction "GPIO6/PME_MODE_SEL_40") (pintype "unspecified+no_connect"))
    )
    (net (code "337") (name "unconnected-(U5-GPIO7-Pad10)") (class "Default")
      (node (ref "U5") (pin "10") (pinfunction "GPIO7_10") (pintype "unspecified+no_connect"))
    )
    (net (code "338") (name "unconnected-(U5-GPIO8-Pad18)") (class "Default")
      (node (ref "U5") (pin "18") (pinfunction "GPIO8_18") (pintype "unspecified+no_connect"))
    )
    (net (code "339") (name "unconnected-(U5-GPIO9-Pad21)") (class "Default")
      (node (ref "U5") (pin "21") (pinfunction "GPIO9_21") (pintype "unspecified+no_connect"))
    )
    (net (code "340") (name "unconnected-(U5-GPIO10-Pad22)") (class "Default")
      (node (ref "U5") (pin "22") (pinfunction "GPIO10_22") (pintype "unspecified+no_connect"))
    )
    (net (code "341") (name "unconnected-(U5-GPIO11-Pad25)") (class "Default")
      (node (ref "U5") (pin "25") (pinfunction "GPIO11_25") (pintype "unspecified+no_connect"))
    )
    (net (code "342") (name "unconnected-(U5-TDO-Pad4)") (class "Default")
      (node (ref "U5") (pin "4") (pinfunction "TDO_4") (pintype "unspecified+no_connect"))
    )
    (net (code "343") (name "unconnected-(U6-MR#-Pad3)") (class "Default")
      (node (ref "U6") (pin "3") (pinfunction "MR#_3") (pintype "input+no_connect"))
    )
    (net (code "344") (name "unconnected-(U8-NC-Pad2)") (class "Default")
      (node (ref "U8") (pin "2") (pinfunction "NC_2") (pintype "unspecified+no_connect"))
    )
    (net (code "345") (name "unconnected-(U8-NC-Pad5)") (class "Default")
      (node (ref "U8") (pin "5") (pinfunction "NC_5") (pintype "unspecified+no_connect"))
    )
    (net (code "346") (name "unconnected-(U9-GPIO2{slash}LED2-Pad33)") (class "Default")
      (node (ref "U9") (pin "33") (pinfunction "GPIO2/LED2_33") (pintype "unspecified+no_connect"))
    )
    (net (code "347") (name "unconnected-(U9-GPIO3{slash}LED3-Pad34)") (class "Default")
      (node (ref "U9") (pin "34") (pinfunction "GPIO3/LED3_34") (pintype "unspecified+no_connect"))
    )
    (net (code "348") (name "unconnected-(U9-GPIO5{slash}PME-Pad38)") (class "Default")
      (node (ref "U9") (pin "38") (pinfunction "GPIO5/PME_38") (pintype "unspecified+no_connect"))
    )
    (net (code "349") (name "unconnected-(U9-GPIO6{slash}PME_MODE_SEL-Pad40)") (class "Default")
      (node (ref "U9") (pin "40") (pinfunction "GPIO6/PME_MODE_SEL_40") (pintype "unspecified+no_connect"))
    )
    (net (code "350") (name "unconnected-(U9-GPIO7-Pad10)") (class "Default")
      (node (ref "U9") (pin "10") (pinfunction "GPIO7_10") (pintype "unspecified+no_connect"))
    )
    (net (code "351") (name "unconnected-(U9-GPIO8-Pad18)") (class "Default")
      (node (ref "U9") (pin "18") (pinfunction "GPIO8_18") (pintype "unspecified+no_connect"))
    )
    (net (code "352") (name "unconnected-(U9-GPIO9-Pad21)") (class "Default")
      (node (ref "U9") (pin "21") (pinfunction "GPIO9_21") (pintype "unspecified+no_connect"))
    )
    (net (code "353") (name "unconnected-(U9-GPIO10-Pad22)") (class "Default")
      (node (ref "U9") (pin "22") (pinfunction "GPIO10_22") (pintype "unspecified+no_connect"))
    )
    (net (code "354") (name "unconnected-(U9-GPIO11-Pad25)") (class "Default")
      (node (ref "U9") (pin "25") (pinfunction "GPIO11_25") (pintype "unspecified+no_connect"))
    )
    (net (code "355") (name "unconnected-(U9-TDO-Pad4)") (class "Default")
      (node (ref "U9") (pin "4") (pinfunction "TDO_4") (pintype "unspecified+no_connect"))
    )
    (net (code "356") (name "unconnected-(U10-MR#-Pad3)") (class "Default")
      (node (ref "U10") (pin "3") (pinfunction "MR#_3") (pintype "input+no_connect"))
    )
    (net (code "357") (name "unconnected-(U12-NC-Pad2)") (class "Default")
      (node (ref "U12") (pin "2") (pinfunction "NC_2") (pintype "unspecified+no_connect"))
    )
    (net (code "358") (name "unconnected-(U12-NC-Pad5)") (class "Default")
      (node (ref "U12") (pin "5") (pinfunction "NC_5") (pintype "unspecified+no_connect"))
    )
    (net (code "359") (name "unconnected-(USB1-SBU1-PadA8)") (class "Default")
      (node (ref "USB1") (pin "A8") (pinfunction "SBU1_A8") (pintype "input+no_connect"))
    )
    (net (code "360") (name "unconnected-(USB1-SBU2-PadB8)") (class "Default")
      (node (ref "USB1") (pin "B8") (pinfunction "SBU2_B8") (pintype "input+no_connect"))
    )
  )
)
